# lamp_controller.net
KiCad netlist of a schematic drawn in Altium Designer
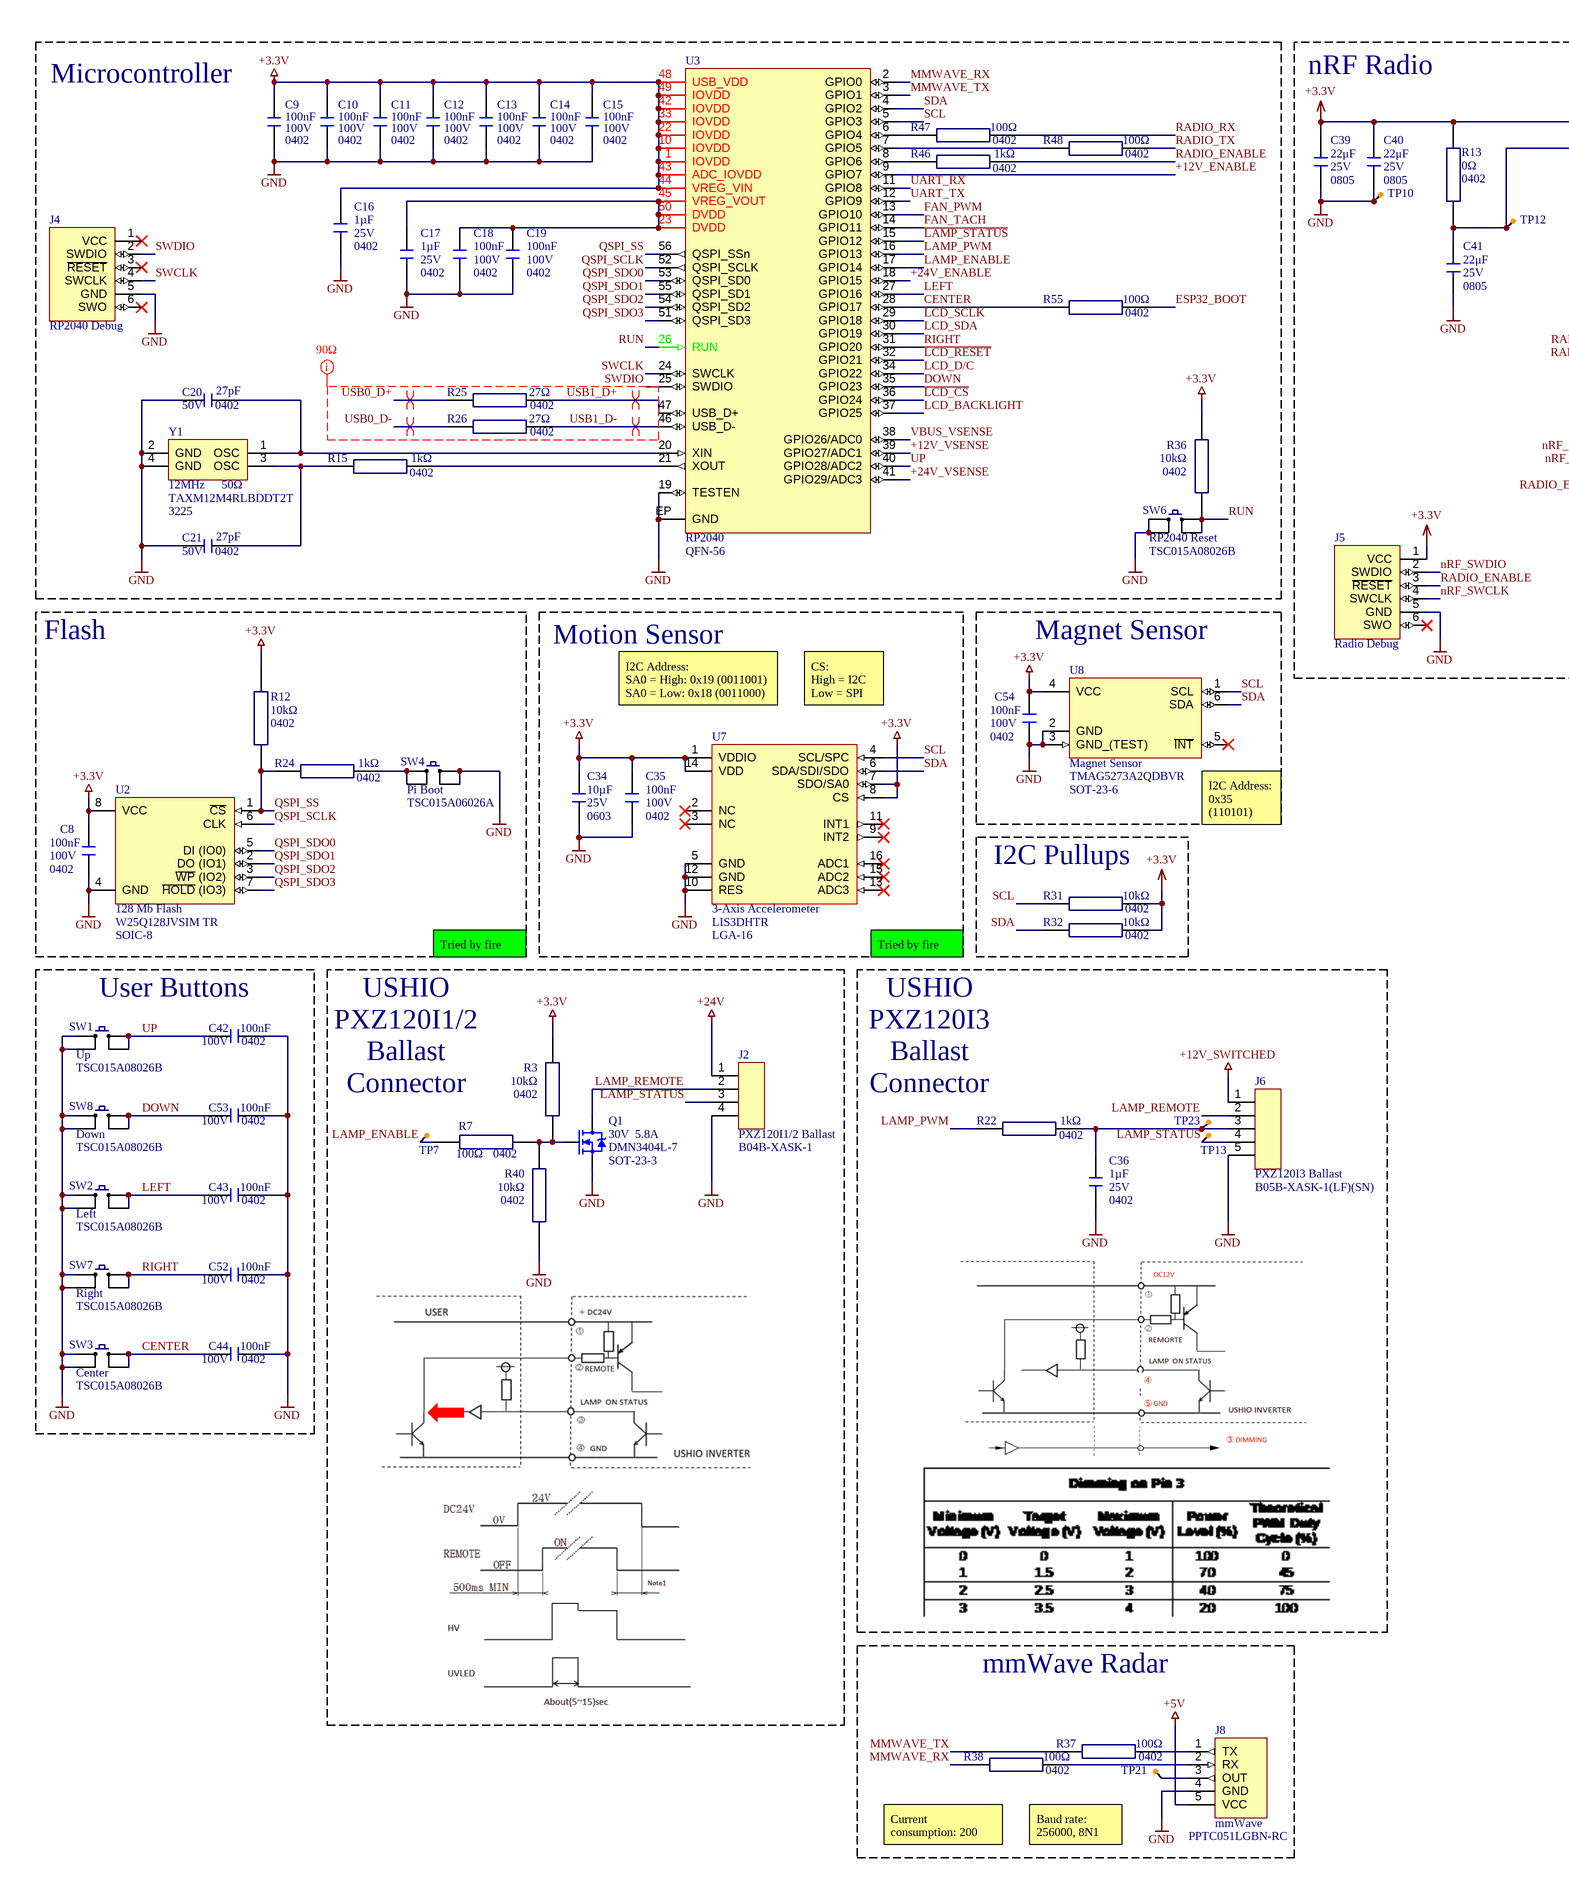
[diagram p0: lamp_controller.SchDoc, left]
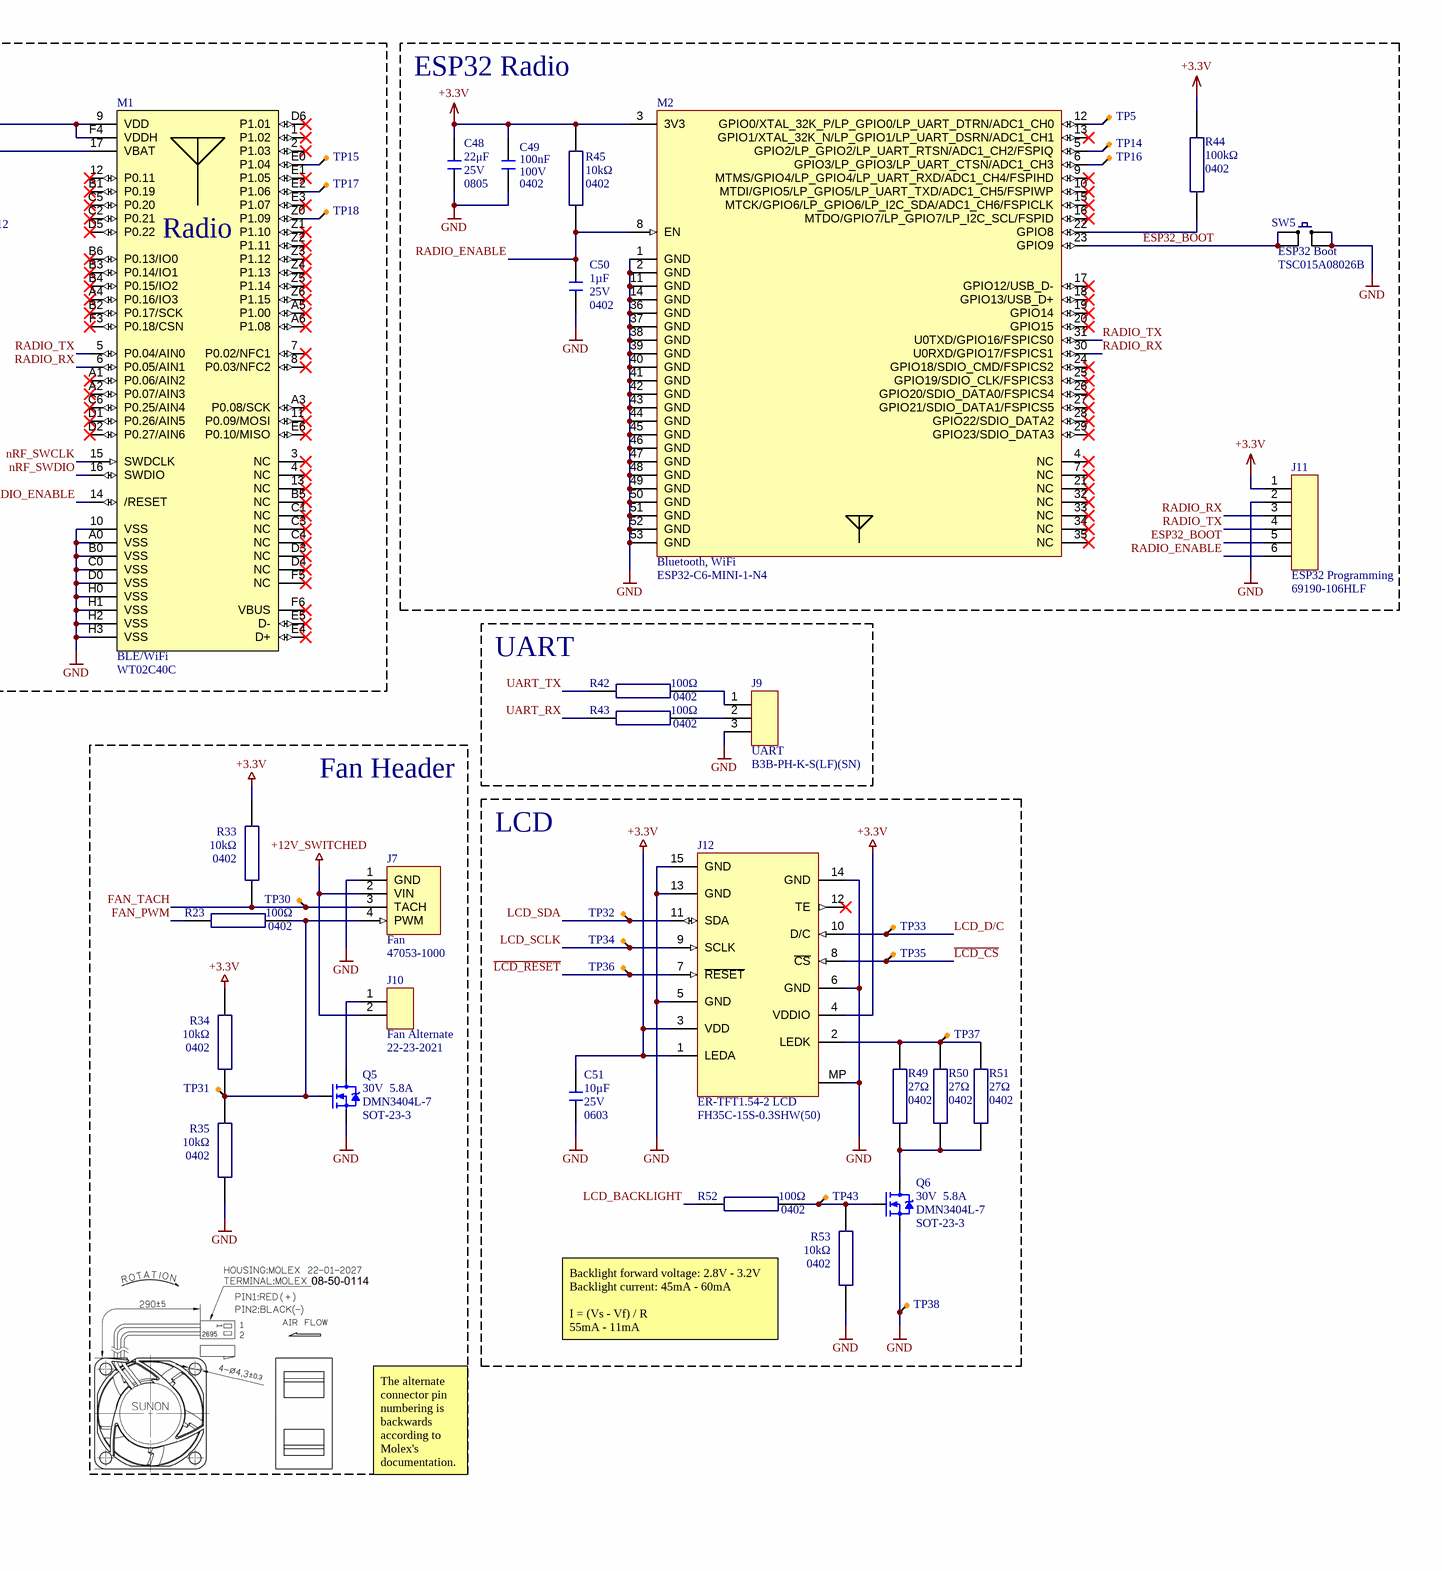
[diagram p1: lamp_controller.SchDoc, right]

(export (version "E")
  (design (tool "Eeschema 10.0.6"))
  (components
    (comp (ref "C8")
      (value "100nF")
      (footprint "0402_capacitor")
      (description "100 nF, 100 V, X7R, 0402 Chip capacitor")
      (fields
        (field (name "MANUFACTURER") "Murata")
        (field (name "CASE/PACKAGE") "0402")
        (field (name "MANUFACTURER PART NUMBER") "GRM155R62A104KE14D")
        (field (name "RATED DC VOLTAGE (URDC)") "100V")
      )
      (libsource (lib "lamp_controller") (part "GRM155R62A104KE14D"))
    )
    (comp (ref "C9")
      (value "100nF")
      (footprint "0402_capacitor")
      (description "100 nF, 100 V, X7R, 0402 Chip capacitor")
      (fields
        (field (name "MANUFACTURER") "Murata")
        (field (name "CASE/PACKAGE") "0402")
        (field (name "MANUFACTURER PART NUMBER") "GRM155R62A104KE14D")
        (field (name "RATED DC VOLTAGE (URDC)") "100V")
      )
      (libsource (lib "lamp_controller") (part "GRM155R62A104KE14D"))
    )
    (comp (ref "C10")
      (value "100nF")
      (footprint "0402_capacitor")
      (description "100 nF, 100 V, X7R, 0402 Chip capacitor")
      (fields
        (field (name "MANUFACTURER") "Murata")
        (field (name "CASE/PACKAGE") "0402")
        (field (name "MANUFACTURER PART NUMBER") "GRM155R62A104KE14D")
        (field (name "RATED DC VOLTAGE (URDC)") "100V")
      )
      (libsource (lib "lamp_controller") (part "GRM155R62A104KE14D"))
    )
    (comp (ref "C11")
      (value "100nF")
      (footprint "0402_capacitor")
      (description "100 nF, 100 V, X7R, 0402 Chip capacitor")
      (fields
        (field (name "MANUFACTURER") "Murata")
        (field (name "CASE/PACKAGE") "0402")
        (field (name "MANUFACTURER PART NUMBER") "GRM155R62A104KE14D")
        (field (name "RATED DC VOLTAGE (URDC)") "100V")
      )
      (libsource (lib "lamp_controller") (part "GRM155R62A104KE14D"))
    )
    (comp (ref "C12")
      (value "100nF")
      (footprint "0402_capacitor")
      (description "100 nF, 100 V, X7R, 0402 Chip capacitor")
      (fields
        (field (name "MANUFACTURER") "Murata")
        (field (name "CASE/PACKAGE") "0402")
        (field (name "MANUFACTURER PART NUMBER") "GRM155R62A104KE14D")
        (field (name "RATED DC VOLTAGE (URDC)") "100V")
      )
      (libsource (lib "lamp_controller") (part "GRM155R62A104KE14D"))
    )
    (comp (ref "C13")
      (value "100nF")
      (footprint "0402_capacitor")
      (description "100 nF, 100 V, X7R, 0402 Chip capacitor")
      (fields
        (field (name "MANUFACTURER") "Murata")
        (field (name "CASE/PACKAGE") "0402")
        (field (name "MANUFACTURER PART NUMBER") "GRM155R62A104KE14D")
        (field (name "RATED DC VOLTAGE (URDC)") "100V")
      )
      (libsource (lib "lamp_controller") (part "GRM155R62A104KE14D"))
    )
    (comp (ref "C14")
      (value "100nF")
      (footprint "0402_capacitor")
      (description "100 nF, 100 V, X7R, 0402 Chip capacitor")
      (fields
        (field (name "MANUFACTURER") "Murata")
        (field (name "CASE/PACKAGE") "0402")
        (field (name "MANUFACTURER PART NUMBER") "GRM155R62A104KE14D")
        (field (name "RATED DC VOLTAGE (URDC)") "100V")
      )
      (libsource (lib "lamp_controller") (part "GRM155R62A104KE14D"))
    )
    (comp (ref "C15")
      (value "100nF")
      (footprint "0402_capacitor")
      (description "100 nF, 100 V, X7R, 0402 Chip capacitor")
      (fields
        (field (name "MANUFACTURER") "Murata")
        (field (name "CASE/PACKAGE") "0402")
        (field (name "MANUFACTURER PART NUMBER") "GRM155R62A104KE14D")
        (field (name "RATED DC VOLTAGE (URDC)") "100V")
      )
      (libsource (lib "lamp_controller") (part "GRM155R62A104KE14D"))
    )
    (comp (ref "C16")
      (value "GRM155R61E105KA12D")
      (footprint "0402_capacitor")
      (description "1 µF, 25 V, X5R, 0402 Chip capacitor")
      (fields
        (field (name "MANUFACTURER") "Murata")
        (field (name "HOUSE_PART_NUMBER") "C-1uF-0402-002")
        (field (name "SIZE CODE") "0402")
        (field (name "CAPACITANCE") "1µF")
        (field (name "VOLTAGE") "25V")
      )
      (libsource (lib "lamp_controller") (part "GRM155R61E105KA12D"))
    )
    (comp (ref "C17")
      (value "GRM155R61E105KA12D")
      (footprint "0402_capacitor")
      (description "1 µF, 25 V, X5R, 0402 Chip capacitor")
      (fields
        (field (name "MANUFACTURER") "Murata")
        (field (name "HOUSE_PART_NUMBER") "C-1uF-0402-002")
        (field (name "SIZE CODE") "0402")
        (field (name "CAPACITANCE") "1µF")
        (field (name "VOLTAGE") "25V")
      )
      (libsource (lib "lamp_controller") (part "GRM155R61E105KA12D"))
    )
    (comp (ref "C18")
      (value "100nF")
      (footprint "0402_capacitor")
      (description "100 nF, 100 V, X7R, 0402 Chip capacitor")
      (fields
        (field (name "MANUFACTURER") "Murata")
        (field (name "CASE/PACKAGE") "0402")
        (field (name "MANUFACTURER PART NUMBER") "GRM155R62A104KE14D")
        (field (name "RATED DC VOLTAGE (URDC)") "100V")
      )
      (libsource (lib "lamp_controller") (part "GRM155R62A104KE14D"))
    )
    (comp (ref "C19")
      (value "100nF")
      (footprint "0402_capacitor")
      (description "100 nF, 100 V, X7R, 0402 Chip capacitor")
      (fields
        (field (name "MANUFACTURER") "Murata")
        (field (name "CASE/PACKAGE") "0402")
        (field (name "MANUFACTURER PART NUMBER") "GRM155R62A104KE14D")
        (field (name "RATED DC VOLTAGE (URDC)") "100V")
      )
      (libsource (lib "lamp_controller") (part "GRM155R62A104KE14D"))
    )
    (comp (ref "C20")
      (value "27pF")
      (footprint "0402_capacitor")
      (description "27 pF, 25 V, X7R, 0402 Chip capacitor")
      (fields
        (field (name "MANUFACTURER") "Yageo")
        (field (name "MANUFACTURER PART NUMBER") "CC0402JRNPO9BN270")
        (field (name "CASE/PACKAGE") "0402")
        (field (name "VOLTAGE RATING (DC)") "50V")
      )
      (libsource (lib "lamp_controller") (part "CC0402JRNPO9BN270"))
    )
    (comp (ref "C21")
      (value "27pF")
      (footprint "0402_capacitor")
      (description "27 pF, 25 V, X7R, 0402 Chip capacitor")
      (fields
        (field (name "MANUFACTURER") "Yageo")
        (field (name "MANUFACTURER PART NUMBER") "CC0402JRNPO9BN270")
        (field (name "CASE/PACKAGE") "0402")
        (field (name "VOLTAGE RATING (DC)") "50V")
      )
      (libsource (lib "lamp_controller") (part "CC0402JRNPO9BN270"))
    )
    (comp (ref "C34")
      (value "10µF")
      (footprint "0603_capacitor")
      (description "10 µF, 25 V, X5R, 0603 Chip capacitor")
      (fields
        (field (name "MANUFACTURER") "Samsung")
        (field (name "CASE/PACKAGE") "0603")
        (field (name "TOLERANCE") "20%")
        (field (name "VOLTAGE RATING") "25V")
      )
      (libsource (lib "lamp_controller") (part "CL10A106MA8NRNC"))
    )
    (comp (ref "C35")
      (value "100nF")
      (footprint "0402_capacitor")
      (description "100 nF, 100 V, X7R, 0402 Chip capacitor")
      (fields
        (field (name "MANUFACTURER") "Murata")
        (field (name "CASE/PACKAGE") "0402")
        (field (name "MANUFACTURER PART NUMBER") "GRM155R62A104KE14D")
        (field (name "RATED DC VOLTAGE (URDC)") "100V")
      )
      (libsource (lib "lamp_controller") (part "GRM155R62A104KE14D"))
    )
    (comp (ref "C36")
      (value "GRM155R61E105KA12D")
      (footprint "0402_capacitor")
      (description "1 µF, 25 V, X5R, 0402 Chip capacitor")
      (fields
        (field (name "MANUFACTURER") "Murata")
        (field (name "HOUSE_PART_NUMBER") "C-1uF-0402-002")
        (field (name "SIZE CODE") "0402")
        (field (name "CAPACITANCE") "1µF")
        (field (name "VOLTAGE") "25V")
      )
      (libsource (lib "lamp_controller") (part "GRM155R61E105KA12D"))
    )
    (comp (ref "C39")
      (value "22μF")
      (footprint "0805_capacitor")
      (description "22 μF, 25 V, X5R, 0805 Chip capacitor")
      (fields
        (field (name "MANUFACTURER") "Murata")
        (field (name "MANUFACTURER PART NUMBER") "GRT21BR61E226ME13L")
        (field (name "RATED DC VOLTAGE (URDC)") "25V")
        (field (name "CASE/PACKAGE") "0805")
      )
      (libsource (lib "lamp_controller") (part "GRT21BR61E226ME13L"))
    )
    (comp (ref "C40")
      (value "22μF")
      (footprint "0805_capacitor")
      (description "22 μF, 25 V, X5R, 0805 Chip capacitor")
      (fields
        (field (name "MANUFACTURER") "Murata")
        (field (name "MANUFACTURER PART NUMBER") "GRT21BR61E226ME13L")
        (field (name "RATED DC VOLTAGE (URDC)") "25V")
        (field (name "CASE/PACKAGE") "0805")
      )
      (libsource (lib "lamp_controller") (part "GRT21BR61E226ME13L"))
    )
    (comp (ref "C41")
      (value "22μF")
      (footprint "0805_capacitor")
      (description "22 μF, 25 V, X5R, 0805 Chip capacitor")
      (fields
        (field (name "MANUFACTURER") "Murata")
        (field (name "MANUFACTURER PART NUMBER") "GRT21BR61E226ME13L")
        (field (name "RATED DC VOLTAGE (URDC)") "25V")
        (field (name "CASE/PACKAGE") "0805")
      )
      (libsource (lib "lamp_controller") (part "GRT21BR61E226ME13L"))
    )
    (comp (ref "C42")
      (value "100nF")
      (footprint "0402_capacitor")
      (description "100 nF, 100 V, X7R, 0402 Chip capacitor")
      (fields
        (field (name "MANUFACTURER") "Murata")
        (field (name "CASE/PACKAGE") "0402")
        (field (name "MANUFACTURER PART NUMBER") "GRM155R62A104KE14D")
        (field (name "RATED DC VOLTAGE (URDC)") "100V")
      )
      (libsource (lib "lamp_controller") (part "GRM155R62A104KE14D"))
    )
    (comp (ref "C43")
      (value "100nF")
      (footprint "0402_capacitor")
      (description "100 nF, 100 V, X7R, 0402 Chip capacitor")
      (fields
        (field (name "MANUFACTURER") "Murata")
        (field (name "CASE/PACKAGE") "0402")
        (field (name "MANUFACTURER PART NUMBER") "GRM155R62A104KE14D")
        (field (name "RATED DC VOLTAGE (URDC)") "100V")
      )
      (libsource (lib "lamp_controller") (part "GRM155R62A104KE14D"))
    )
    (comp (ref "C44")
      (value "100nF")
      (footprint "0402_capacitor")
      (description "100 nF, 100 V, X7R, 0402 Chip capacitor")
      (fields
        (field (name "MANUFACTURER") "Murata")
        (field (name "CASE/PACKAGE") "0402")
        (field (name "MANUFACTURER PART NUMBER") "GRM155R62A104KE14D")
        (field (name "RATED DC VOLTAGE (URDC)") "100V")
      )
      (libsource (lib "lamp_controller") (part "GRM155R62A104KE14D"))
    )
    (comp (ref "C48")
      (value "22μF")
      (footprint "0805_capacitor")
      (description "22 μF, 25 V, X5R, 0805 Chip capacitor")
      (fields
        (field (name "MANUFACTURER") "Murata")
        (field (name "MANUFACTURER PART NUMBER") "GRT21BR61E226ME13L")
        (field (name "RATED DC VOLTAGE (URDC)") "25V")
        (field (name "CASE/PACKAGE") "0805")
      )
      (libsource (lib "lamp_controller") (part "GRT21BR61E226ME13L"))
    )
    (comp (ref "C49")
      (value "100nF")
      (footprint "0402_capacitor")
      (description "100 nF, 100 V, X7R, 0402 Chip capacitor")
      (fields
        (field (name "MANUFACTURER") "Murata")
        (field (name "CASE/PACKAGE") "0402")
        (field (name "MANUFACTURER PART NUMBER") "GRM155R62A104KE14D")
        (field (name "RATED DC VOLTAGE (URDC)") "100V")
      )
      (libsource (lib "lamp_controller") (part "GRM155R62A104KE14D"))
    )
    (comp (ref "C50")
      (value "GRM155R61E105KA12D")
      (footprint "0402_capacitor")
      (description "1 µF, 25 V, X5R, 0402 Chip capacitor")
      (fields
        (field (name "MANUFACTURER") "Murata")
        (field (name "HOUSE_PART_NUMBER") "C-1uF-0402-002")
        (field (name "SIZE CODE") "0402")
        (field (name "CAPACITANCE") "1µF")
        (field (name "VOLTAGE") "25V")
      )
      (libsource (lib "lamp_controller") (part "GRM155R61E105KA12D"))
    )
    (comp (ref "C51")
      (value "10µF")
      (footprint "0603_capacitor")
      (description "10 µF, 25 V, X5R, 0603 Chip capacitor")
      (fields
        (field (name "MANUFACTURER") "Samsung")
        (field (name "CASE/PACKAGE") "0603")
        (field (name "TOLERANCE") "20%")
        (field (name "VOLTAGE RATING") "25V")
      )
      (libsource (lib "lamp_controller") (part "CL10A106MA8NRNC"))
    )
    (comp (ref "C52")
      (value "100nF")
      (footprint "0402_capacitor")
      (description "100 nF, 100 V, X7R, 0402 Chip capacitor")
      (fields
        (field (name "MANUFACTURER") "Murata")
        (field (name "CASE/PACKAGE") "0402")
        (field (name "MANUFACTURER PART NUMBER") "GRM155R62A104KE14D")
        (field (name "RATED DC VOLTAGE (URDC)") "100V")
      )
      (libsource (lib "lamp_controller") (part "GRM155R62A104KE14D"))
    )
    (comp (ref "C53")
      (value "100nF")
      (footprint "0402_capacitor")
      (description "100 nF, 100 V, X7R, 0402 Chip capacitor")
      (fields
        (field (name "MANUFACTURER") "Murata")
        (field (name "CASE/PACKAGE") "0402")
        (field (name "MANUFACTURER PART NUMBER") "GRM155R62A104KE14D")
        (field (name "RATED DC VOLTAGE (URDC)") "100V")
      )
      (libsource (lib "lamp_controller") (part "GRM155R62A104KE14D"))
    )
    (comp (ref "C54")
      (value "100nF")
      (footprint "0402_capacitor")
      (description "100 nF, 100 V, X7R, 0402 Chip capacitor")
      (fields
        (field (name "MANUFACTURER") "Murata")
        (field (name "CASE/PACKAGE") "0402")
        (field (name "MANUFACTURER PART NUMBER") "GRM155R62A104KE14D")
        (field (name "RATED DC VOLTAGE (URDC)") "100V")
      )
      (libsource (lib "lamp_controller") (part "GRM155R62A104KE14D"))
    )
    (comp (ref "J2")
      (value "PXZ120I1/2 Ballast")
      (footprint "B04B-XASK-1")
      (description "4-pin JST XA header, 2.5mm pitch, through-hole")
      (fields (field (name "MANUFACTURER") "JST") (field (name "MANUFACTURER PART NUMBER") "B04B-XASK-1"))
      (libsource (lib "lamp_controller") (part "B04B-XASK-1"))
    )
    (comp (ref "J4")
      (value "RP2040 Debug")
      (footprint "debug_header_dual")
      (description "Tag-connect 6-pin pogo header")
      (libsource (lib "lamp_controller") (part "debug_header"))
    )
    (comp (ref "J5")
      (value "Radio Debug")
      (footprint "debug_header_dual")
      (description "Tag-connect 6-pin pogo header")
      (libsource (lib "lamp_controller") (part "debug_header"))
    )
    (comp (ref "J6")
      (value "PXZ120I3 Ballast")
      (footprint "B05B-XASK-1")
      (description "5-Pin JST XA header, 2.5mm pitch, through-hole")
      (fields
        (field (name "MANUFACTURER") "JST")
        (field (name "MANUFACTURER PART NUMBER") "B05B-XASK-1(LF)(SN)")
      )
      (libsource (lib "lamp_controller") (part "B05B-XASK-1(LF)(SN)"))
    )
    (comp (ref "J7")
      (value "Fan")
      (footprint "470531000")
      (description "4-pin PC Fan connector")
      (fields (field (name "MANUFACTURER") "Molex") (field (name "MANUFACTURER PART NUMBER") "47053-1000"))
      (libsource (lib "lamp_controller") (part "470531000"))
    )
    (comp (ref "J8")
      (value "mmWave")
      (footprint "radar_angled_1")
      (description "5-Pin angled female header with mmWave radar board.")
      (fields
        (field (name "MANUFACTURER") "Sullins")
        (field (name "MANUFACTURER PART NUMBER") "PPTC051LGBN-RC")
      )
      (libsource (lib "lamp_controller") (part "PPTC051LGBN-RC"))
    )
    (comp (ref "J9")
      (value "UART")
      (footprint "B3B-PH-K-S(LF)(SN)")
      (description "3-Pin JST PH header, 2mm pitch, Through Hole")
      (fields
        (field (name "MANUFACTURER") "JST")
        (field (name "MANUFACTURER PART NUMBER") "B3B-PH-K-S(LF)(SN)")
      )
      (libsource (lib "lamp_controller") (part "B3B-PH-K-S(LF)(SN)"))
    )
    (comp (ref "J10")
      (value "Fan Alternate")
      (footprint "22012027")
      (description "2-Pin 0.1\" header, through-hole")
      (fields (field (name "MANUFACTURER") "Molex") (field (name "MANUFACTURER PART NUMBER") "22-23-2021"))
      (libsource (lib "lamp_controller") (part "22-23-2021"))
    )
    (comp (ref "J11")
      (value "ESP32 Programming")
      (footprint "69190-106HLF")
      (description "6-Pin 0.1\" unshrouded header pins")
      (fields
        (field (name "MANUFACTURER") "Amphenol ICC / FCI")
        (field (name "MANUFACTURER PART NUMBER") "69190-106HLF")
      )
      (libsource (lib "lamp_controller") (part "69190-106HLF"))
    )
    (comp (ref "J12")
      (value "ER-TFT1.54-2 LCD")
      (footprint "FH35C-15S-0.3SHW(50)")
      (description "ER-TFT1.54-2 1.54\" IPS LCD, 240x240, ST7789 controller, FH35C-15S-0.3SHW(50) connector")
      (fields
        (field (name "MANUFACTURER") "HRS")
        (field (name "MANUFACTURER PART NUMBER") "FH35C-15S-0.3SHW(50)")
      )
      (libsource (lib "lamp_controller") (part "LCD Connector"))
    )
    (comp (ref "M1")
      (value "BLE/WiFi")
      (footprint "WT02C40C")
      (description "nRF5340 BLE/WIFI module")
      (fields (field (name "MANUFACTURER PART NUMBER") "WT02C40C"))
      (libsource (lib "lamp_controller") (part "WT02C40C"))
    )
    (comp (ref "M2")
      (value "Bluetooth, WiFi")
      (footprint "ESP32-C6-MINI-1")
      (description "ESP32-C6 chipset, PCB antenna, SMD-53")
      (fields
        (field (name "MANUFACTURER") "Espressif Systems")
        (field (name "MANUFACTURER PART NUMBER") "ESP32-C6-MINI-1-N4")
      )
      (libsource (lib "lamp_controller") (part "ESP32-C6-MINI-1-N4"))
    )
    (comp (ref "Q1")
      (value "DMN3404L-7")
      (footprint "SOT-23-3")
      (description "N-FET, 30 V, 5.8 A, SOT-23-3")
      (fields
        (field (name "MANUFACTURER") "Diodes")
        (field (name "PACKAGE") "SOT-23-3")
        (field (name "DS BREAKDOWN VOLTAGE-MIN") "30V")
        (field (name "DRAIN CURRENT-MAX (ID)") "5.8A")
        (field (name "MANUFACTURER PART NUMBER") "DMN3404L-7")
      )
      (libsource (lib "lamp_controller") (part "DMN3404L-7"))
    )
    (comp (ref "Q5")
      (value "DMN3404L-7")
      (footprint "SOT-23-3")
      (description "N-FET, 30 V, 5.8 A, SOT-23-3")
      (fields
        (field (name "MANUFACTURER") "Diodes")
        (field (name "PACKAGE") "SOT-23-3")
        (field (name "DS BREAKDOWN VOLTAGE-MIN") "30V")
        (field (name "DRAIN CURRENT-MAX (ID)") "5.8A")
        (field (name "MANUFACTURER PART NUMBER") "DMN3404L-7")
      )
      (libsource (lib "lamp_controller") (part "DMN3404L-7"))
    )
    (comp (ref "Q6")
      (value "DMN3404L-7")
      (footprint "SOT-23-3")
      (description "N-FET, 30 V, 5.8 A, SOT-23-3")
      (fields
        (field (name "MANUFACTURER") "Diodes")
        (field (name "PACKAGE") "SOT-23-3")
        (field (name "DS BREAKDOWN VOLTAGE-MIN") "30V")
        (field (name "DRAIN CURRENT-MAX (ID)") "5.8A")
        (field (name "MANUFACTURER PART NUMBER") "DMN3404L-7")
      )
      (libsource (lib "lamp_controller") (part "DMN3404L-7"))
    )
    (comp (ref "R3")
      (value "RMCF0402FT10K0")
      (footprint "0402_resistor")
      (description "10 kΩ, 0402 Chip resistor")
      (fields
        (field (name "MANUFACTURER") "Stackpole Electronics")
        (field (name "TOLERANCE") "1%")
        (field (name "CASE CODE (IMPERIAL)") "0402")
        (field (name "RESISTANCE") "10kΩ")
      )
      (libsource (lib "lamp_controller") (part "RMCF0402FT10K0"))
    )
    (comp (ref "R7")
      (value "RMCF0402FT100R")
      (footprint "0402_resistor")
      (description "100 Ω, 0402 Chip resistor")
      (fields
        (field (name "MANUFACTURER") "Stackpole Electronics")
        (field (name "TOLERANCE") "1%")
        (field (name "CASE CODE (IMPERIAL)") "0402")
        (field (name "RESISTANCE") "100Ω")
      )
      (libsource (lib "lamp_controller") (part "RMCF0402FT100R"))
    )
    (comp (ref "R12")
      (value "RMCF0402FT10K0")
      (footprint "0402_resistor")
      (description "10 kΩ, 0402 Chip resistor")
      (fields
        (field (name "MANUFACTURER") "Stackpole Electronics")
        (field (name "TOLERANCE") "1%")
        (field (name "CASE CODE (IMPERIAL)") "0402")
        (field (name "RESISTANCE") "10kΩ")
      )
      (libsource (lib "lamp_controller") (part "RMCF0402FT10K0"))
    )
    (comp (ref "R13")
      (value "RMCF0402ZT0R00")
      (footprint "0402_resistor")
      (description "0 Ω, 0402 Jumper")
      (fields
        (field (name "MANUFACTURER") "Stackpole Electronics")
        (field (name "HOUSE_PART_NUMBER") "JP-0402-001")
        (field (name "RESISTANCE") "0Ω")
        (field (name "CASE/PACKAGE") "0402")
      )
      (libsource (lib "lamp_controller") (part "RMCF0402ZT0R00"))
    )
    (comp (ref "R15")
      (value "CR0402-FX-1001GLF")
      (footprint "0402_resistor")
      (description "1 kΩ, 0402 Chip resistor")
      (fields
        (field (name "MANUFACTURER") "Bourns")
        (field (name "TOLERANCE") "1%")
        (field (name "SIZE CODE") "0402")
        (field (name "RESISTANCE") "1kΩ")
      )
      (libsource (lib "lamp_controller") (part "CR0402-FX-1001GLF"))
    )
    (comp (ref "R22")
      (value "CR0402-FX-1001GLF")
      (footprint "0402_resistor")
      (description "1 kΩ, 0402 Chip resistor")
      (fields
        (field (name "MANUFACTURER") "Bourns")
        (field (name "TOLERANCE") "1%")
        (field (name "SIZE CODE") "0402")
        (field (name "RESISTANCE") "1kΩ")
      )
      (libsource (lib "lamp_controller") (part "CR0402-FX-1001GLF"))
    )
    (comp (ref "R23")
      (value "RMCF0402FT100R")
      (footprint "0402_resistor")
      (description "100 Ω, 0402 Chip resistor")
      (fields
        (field (name "MANUFACTURER") "Stackpole Electronics")
        (field (name "TOLERANCE") "1%")
        (field (name "CASE CODE (IMPERIAL)") "0402")
        (field (name "RESISTANCE") "100Ω")
      )
      (libsource (lib "lamp_controller") (part "RMCF0402FT100R"))
    )
    (comp (ref "R24")
      (value "CR0402-FX-1001GLF")
      (footprint "0402_resistor")
      (description "1 kΩ, 0402 Chip resistor")
      (fields
        (field (name "MANUFACTURER") "Bourns")
        (field (name "TOLERANCE") "1%")
        (field (name "SIZE CODE") "0402")
        (field (name "RESISTANCE") "1kΩ")
      )
      (libsource (lib "lamp_controller") (part "CR0402-FX-1001GLF"))
    )
    (comp (ref "R25")
      (value "RMCF0402FT27R0")
      (footprint "0402_resistor")
      (description "27 Ω, 0402 Chip resistor")
      (fields
        (field (name "MANUFACTURER") "Stackpole Electronics")
        (field (name "TOLERANCE") "1%")
        (field (name "RESISTANCE") "27Ω")
        (field (name "SIZE CODE") "0402")
      )
      (libsource (lib "lamp_controller") (part "RMCF0402FT27R0"))
    )
    (comp (ref "R26")
      (value "RMCF0402FT27R0")
      (footprint "0402_resistor")
      (description "27 Ω, 0402 Chip resistor")
      (fields
        (field (name "MANUFACTURER") "Stackpole Electronics")
        (field (name "TOLERANCE") "1%")
        (field (name "RESISTANCE") "27Ω")
        (field (name "SIZE CODE") "0402")
      )
      (libsource (lib "lamp_controller") (part "RMCF0402FT27R0"))
    )
    (comp (ref "R31")
      (value "RMCF0402FT10K0")
      (footprint "0402_resistor")
      (description "10 kΩ, 0402 Chip resistor")
      (fields
        (field (name "MANUFACTURER") "Stackpole Electronics")
        (field (name "TOLERANCE") "1%")
        (field (name "CASE CODE (IMPERIAL)") "0402")
        (field (name "RESISTANCE") "10kΩ")
      )
      (libsource (lib "lamp_controller") (part "RMCF0402FT10K0"))
    )
    (comp (ref "R32")
      (value "RMCF0402FT10K0")
      (footprint "0402_resistor")
      (description "10 kΩ, 0402 Chip resistor")
      (fields
        (field (name "MANUFACTURER") "Stackpole Electronics")
        (field (name "TOLERANCE") "1%")
        (field (name "CASE CODE (IMPERIAL)") "0402")
        (field (name "RESISTANCE") "10kΩ")
      )
      (libsource (lib "lamp_controller") (part "RMCF0402FT10K0"))
    )
    (comp (ref "R33")
      (value "RMCF0402FT10K0")
      (footprint "0402_resistor")
      (description "10 kΩ, 0402 Chip resistor")
      (fields
        (field (name "MANUFACTURER") "Stackpole Electronics")
        (field (name "TOLERANCE") "1%")
        (field (name "CASE CODE (IMPERIAL)") "0402")
        (field (name "RESISTANCE") "10kΩ")
      )
      (libsource (lib "lamp_controller") (part "RMCF0402FT10K0"))
    )
    (comp (ref "R34")
      (value "RMCF0402FT10K0")
      (footprint "0402_resistor")
      (description "10 kΩ, 0402 Chip resistor")
      (fields
        (field (name "MANUFACTURER") "Stackpole Electronics")
        (field (name "TOLERANCE") "1%")
        (field (name "CASE CODE (IMPERIAL)") "0402")
        (field (name "RESISTANCE") "10kΩ")
      )
      (libsource (lib "lamp_controller") (part "RMCF0402FT10K0"))
    )
    (comp (ref "R35")
      (value "RMCF0402FT10K0")
      (footprint "0402_resistor")
      (description "10 kΩ, 0402 Chip resistor")
      (fields
        (field (name "MANUFACTURER") "Stackpole Electronics")
        (field (name "TOLERANCE") "1%")
        (field (name "CASE CODE (IMPERIAL)") "0402")
        (field (name "RESISTANCE") "10kΩ")
      )
      (libsource (lib "lamp_controller") (part "RMCF0402FT10K0"))
    )
    (comp (ref "R36")
      (value "RMCF0402FT10K0")
      (footprint "0402_resistor")
      (description "10 kΩ, 0402 Chip resistor")
      (fields
        (field (name "MANUFACTURER") "Stackpole Electronics")
        (field (name "TOLERANCE") "1%")
        (field (name "CASE CODE (IMPERIAL)") "0402")
        (field (name "RESISTANCE") "10kΩ")
      )
      (libsource (lib "lamp_controller") (part "RMCF0402FT10K0"))
    )
    (comp (ref "R37")
      (value "RMCF0402FT100R")
      (footprint "0402_resistor")
      (description "100 Ω, 0402 Chip resistor")
      (fields
        (field (name "MANUFACTURER") "Stackpole Electronics")
        (field (name "TOLERANCE") "1%")
        (field (name "CASE CODE (IMPERIAL)") "0402")
        (field (name "RESISTANCE") "100Ω")
      )
      (libsource (lib "lamp_controller") (part "RMCF0402FT100R"))
    )
    (comp (ref "R38")
      (value "RMCF0402FT100R")
      (footprint "0402_resistor")
      (description "100 Ω, 0402 Chip resistor")
      (fields
        (field (name "MANUFACTURER") "Stackpole Electronics")
        (field (name "TOLERANCE") "1%")
        (field (name "CASE CODE (IMPERIAL)") "0402")
        (field (name "RESISTANCE") "100Ω")
      )
      (libsource (lib "lamp_controller") (part "RMCF0402FT100R"))
    )
    (comp (ref "R40")
      (value "RMCF0402FT10K0")
      (footprint "0402_resistor")
      (description "10 kΩ, 0402 Chip resistor")
      (fields
        (field (name "MANUFACTURER") "Stackpole Electronics")
        (field (name "TOLERANCE") "1%")
        (field (name "CASE CODE (IMPERIAL)") "0402")
        (field (name "RESISTANCE") "10kΩ")
      )
      (libsource (lib "lamp_controller") (part "RMCF0402FT10K0"))
    )
    (comp (ref "R42")
      (value "RMCF0402FT100R")
      (footprint "0402_resistor")
      (description "100 Ω, 0402 Chip resistor")
      (fields
        (field (name "MANUFACTURER") "Stackpole Electronics")
        (field (name "TOLERANCE") "1%")
        (field (name "CASE CODE (IMPERIAL)") "0402")
        (field (name "RESISTANCE") "100Ω")
      )
      (libsource (lib "lamp_controller") (part "RMCF0402FT100R"))
    )
    (comp (ref "R43")
      (value "RMCF0402FT100R")
      (footprint "0402_resistor")
      (description "100 Ω, 0402 Chip resistor")
      (fields
        (field (name "MANUFACTURER") "Stackpole Electronics")
        (field (name "TOLERANCE") "1%")
        (field (name "CASE CODE (IMPERIAL)") "0402")
        (field (name "RESISTANCE") "100Ω")
      )
      (libsource (lib "lamp_controller") (part "RMCF0402FT100R"))
    )
    (comp (ref "R44")
      (value "100kΩ")
      (footprint "0402_resistor")
      (description "100 kΩ, 0402 Chip resistor")
      (fields
        (field (name "MANUFACTURER") "Stackpole Electronics")
        (field (name "MANUFACTURER PART NUMBER") "RMCF0402FT100K")
        (field (name "CASE/PACKAGE") "0402")
      )
      (libsource (lib "lamp_controller") (part "RMCF0402FT100K"))
    )
    (comp (ref "R45")
      (value "RMCF0402FT10K0")
      (footprint "0402_resistor")
      (description "10 kΩ, 0402 Chip resistor")
      (fields
        (field (name "MANUFACTURER") "Stackpole Electronics")
        (field (name "TOLERANCE") "1%")
        (field (name "CASE CODE (IMPERIAL)") "0402")
        (field (name "RESISTANCE") "10kΩ")
      )
      (libsource (lib "lamp_controller") (part "RMCF0402FT10K0"))
    )
    (comp (ref "R46")
      (value "CR0402-FX-1001GLF")
      (footprint "0402_resistor")
      (description "1 kΩ, 0402 Chip resistor")
      (fields
        (field (name "MANUFACTURER") "Bourns")
        (field (name "TOLERANCE") "1%")
        (field (name "SIZE CODE") "0402")
        (field (name "RESISTANCE") "1kΩ")
      )
      (libsource (lib "lamp_controller") (part "CR0402-FX-1001GLF"))
    )
    (comp (ref "R47")
      (value "RMCF0402FT100R")
      (footprint "0402_resistor")
      (description "100 Ω, 0402 Chip resistor")
      (fields
        (field (name "MANUFACTURER") "Stackpole Electronics")
        (field (name "TOLERANCE") "1%")
        (field (name "CASE CODE (IMPERIAL)") "0402")
        (field (name "RESISTANCE") "100Ω")
      )
      (libsource (lib "lamp_controller") (part "RMCF0402FT100R"))
    )
    (comp (ref "R48")
      (value "RMCF0402FT100R")
      (footprint "0402_resistor")
      (description "100 Ω, 0402 Chip resistor")
      (fields
        (field (name "MANUFACTURER") "Stackpole Electronics")
        (field (name "TOLERANCE") "1%")
        (field (name "CASE CODE (IMPERIAL)") "0402")
        (field (name "RESISTANCE") "100Ω")
      )
      (libsource (lib "lamp_controller") (part "RMCF0402FT100R"))
    )
    (comp (ref "R49")
      (value "RMCF0402FT27R0")
      (footprint "0402_resistor")
      (description "27 Ω, 0402 Chip resistor")
      (fields
        (field (name "MANUFACTURER") "Stackpole Electronics")
        (field (name "TOLERANCE") "1%")
        (field (name "RESISTANCE") "27Ω")
        (field (name "SIZE CODE") "0402")
      )
      (libsource (lib "lamp_controller") (part "RMCF0402FT27R0"))
    )
    (comp (ref "R50")
      (value "RMCF0402FT27R0")
      (footprint "0402_resistor")
      (description "27 Ω, 0402 Chip resistor")
      (fields
        (field (name "MANUFACTURER") "Stackpole Electronics")
        (field (name "TOLERANCE") "1%")
        (field (name "RESISTANCE") "27Ω")
        (field (name "SIZE CODE") "0402")
      )
      (libsource (lib "lamp_controller") (part "RMCF0402FT27R0"))
    )
    (comp (ref "R51")
      (value "RMCF0402FT27R0")
      (footprint "0402_resistor")
      (description "27 Ω, 0402 Chip resistor")
      (fields
        (field (name "MANUFACTURER") "Stackpole Electronics")
        (field (name "TOLERANCE") "1%")
        (field (name "RESISTANCE") "27Ω")
        (field (name "SIZE CODE") "0402")
      )
      (libsource (lib "lamp_controller") (part "RMCF0402FT27R0"))
    )
    (comp (ref "R52")
      (value "RMCF0402FT100R")
      (footprint "0402_resistor")
      (description "100 Ω, 0402 Chip resistor")
      (fields
        (field (name "MANUFACTURER") "Stackpole Electronics")
        (field (name "TOLERANCE") "1%")
        (field (name "CASE CODE (IMPERIAL)") "0402")
        (field (name "RESISTANCE") "100Ω")
      )
      (libsource (lib "lamp_controller") (part "RMCF0402FT100R"))
    )
    (comp (ref "R53")
      (value "RMCF0402FT10K0")
      (footprint "0402_resistor")
      (description "10 kΩ, 0402 Chip resistor")
      (fields
        (field (name "MANUFACTURER") "Stackpole Electronics")
        (field (name "TOLERANCE") "1%")
        (field (name "CASE CODE (IMPERIAL)") "0402")
        (field (name "RESISTANCE") "10kΩ")
      )
      (libsource (lib "lamp_controller") (part "RMCF0402FT10K0"))
    )
    (comp (ref "R55")
      (value "RMCF0402FT100R")
      (footprint "0402_resistor")
      (description "100 Ω, 0402 Chip resistor")
      (fields
        (field (name "MANUFACTURER") "Stackpole Electronics")
        (field (name "TOLERANCE") "1%")
        (field (name "CASE CODE (IMPERIAL)") "0402")
        (field (name "RESISTANCE") "100Ω")
      )
      (libsource (lib "lamp_controller") (part "RMCF0402FT100R"))
    )
    (comp (ref "SW1")
      (value "Up")
      (footprint "TSC015A08026B")
      (description "Tactile switch, SPST")
      (fields
        (field (name "HOUSE_PART_NUMBER") "SW-TAC-4.5-8-260gf")
        (field (name "MANUFACTURER PART NUMBER") "TSC015A08026B")
      )
      (libsource (lib "lamp_controller") (part "TSC015A08026B"))
    )
    (comp (ref "SW2")
      (value "Left")
      (footprint "TSC015A08026B")
      (description "Tactile switch, SPST")
      (fields
        (field (name "HOUSE_PART_NUMBER") "SW-TAC-4.5-8-260gf")
        (field (name "MANUFACTURER PART NUMBER") "TSC015A08026B")
      )
      (libsource (lib "lamp_controller") (part "TSC015A08026B"))
    )
    (comp (ref "SW3")
      (value "Center")
      (footprint "TSC015A08026B")
      (description "Tactile switch, SPST")
      (fields
        (field (name "HOUSE_PART_NUMBER") "SW-TAC-4.5-8-260gf")
        (field (name "MANUFACTURER PART NUMBER") "TSC015A08026B")
      )
      (libsource (lib "lamp_controller") (part "TSC015A08026B"))
    )
    (comp (ref "SW4")
      (value "Pi Boot")
      (footprint "TSC015A06026A")
      (description "Tactile switch, SPST, 6mm tall")
      (fields (field (name "MANUFACTURER PART NUMBER") "TSC015A06026A"))
      (libsource (lib "lamp_controller") (part "TSC015A06026A"))
    )
    (comp (ref "SW5")
      (value "ESP32 Boot")
      (footprint "TSC015A08026B")
      (description "Tactile switch, SPST")
      (fields
        (field (name "HOUSE_PART_NUMBER") "SW-TAC-4.5-8-260gf")
        (field (name "MANUFACTURER PART NUMBER") "TSC015A08026B")
      )
      (libsource (lib "lamp_controller") (part "TSC015A08026B"))
    )
    (comp (ref "SW6")
      (value "RP2040 Reset")
      (footprint "TSC015A08026B")
      (description "Tactile switch, SPST")
      (fields
        (field (name "HOUSE_PART_NUMBER") "SW-TAC-4.5-8-260gf")
        (field (name "MANUFACTURER PART NUMBER") "TSC015A08026B")
      )
      (libsource (lib "lamp_controller") (part "TSC015A08026B"))
    )
    (comp (ref "SW7")
      (value "Right")
      (footprint "TSC015A08026B")
      (description "Tactile switch, SPST")
      (fields
        (field (name "HOUSE_PART_NUMBER") "SW-TAC-4.5-8-260gf")
        (field (name "MANUFACTURER PART NUMBER") "TSC015A08026B")
      )
      (libsource (lib "lamp_controller") (part "TSC015A08026B"))
    )
    (comp (ref "SW8")
      (value "Down")
      (footprint "TSC015A08026B")
      (description "Tactile switch, SPST")
      (fields
        (field (name "HOUSE_PART_NUMBER") "SW-TAC-4.5-8-260gf")
        (field (name "MANUFACTURER PART NUMBER") "TSC015A08026B")
      )
      (libsource (lib "lamp_controller") (part "TSC015A08026B"))
    )
    (comp (ref "TP5")
      (value "*")
      (footprint "test_point-1")
      (description "Test point")
      (libsource (lib "lamp_controller") (part "test_point-1"))
    )
    (comp (ref "TP7")
      (value "Lamp Enable")
      (footprint "test_point-1")
      (description "Test point")
      (libsource (lib "lamp_controller") (part "test_point-1"))
    )
    (comp (ref "TP10")
      (value "GND")
      (footprint "test_point-1")
      (description "Test point")
      (libsource (lib "lamp_controller") (part "test_point-1"))
    )
    (comp (ref "TP12")
      (value "nRF_VBAT")
      (footprint "test_point-1")
      (description "Test point")
      (libsource (lib "lamp_controller") (part "test_point-1"))
    )
    (comp (ref "TP13")
      (value "Lamp Status")
      (footprint "test_point-1")
      (description "Test point")
      (libsource (lib "lamp_controller") (part "test_point-1"))
    )
    (comp (ref "TP14")
      (value "*")
      (footprint "test_point-1")
      (description "Test point")
      (libsource (lib "lamp_controller") (part "test_point-1"))
    )
    (comp (ref "TP15")
      (value "*")
      (footprint "test_point-1")
      (description "Test point")
      (libsource (lib "lamp_controller") (part "test_point-1"))
    )
    (comp (ref "TP16")
      (value "*")
      (footprint "test_point-1")
      (description "Test point")
      (libsource (lib "lamp_controller") (part "test_point-1"))
    )
    (comp (ref "TP17")
      (value "*")
      (footprint "test_point-1")
      (description "Test point")
      (libsource (lib "lamp_controller") (part "test_point-1"))
    )
    (comp (ref "TP18")
      (value "*")
      (footprint "test_point-1")
      (description "Test point")
      (libsource (lib "lamp_controller") (part "test_point-1"))
    )
    (comp (ref "TP21")
      (value "RADAR Out")
      (footprint "test_point-1")
      (description "Test point")
      (libsource (lib "lamp_controller") (part "test_point-1"))
    )
    (comp (ref "TP23")
      (value "nRF_VBAT")
      (footprint "test_point-1")
      (description "Test point")
      (libsource (lib "lamp_controller") (part "test_point-1"))
    )
    (comp (ref "TP30")
      (value "Fan Tach")
      (footprint "test_point-1")
      (description "Test point")
      (libsource (lib "lamp_controller") (part "test_point-1"))
    )
    (comp (ref "TP31")
      (value "Fan PWM")
      (footprint "test_point-1")
      (description "Test point")
      (libsource (lib "lamp_controller") (part "test_point-1"))
    )
    (comp (ref "TP32")
      (value "LCD SDA")
      (footprint "test_point-1")
      (description "Test point")
      (libsource (lib "lamp_controller") (part "test_point-1"))
    )
    (comp (ref "TP33")
      (value "LCD D/C")
      (footprint "test_point-1")
      (description "Test point")
      (libsource (lib "lamp_controller") (part "test_point-1"))
    )
    (comp (ref "TP34")
      (value "LCD SCLK")
      (footprint "test_point-1")
      (description "Test point")
      (libsource (lib "lamp_controller") (part "test_point-1"))
    )
    (comp (ref "TP35")
      (value "LCD CS")
      (footprint "test_point-1")
      (description "Test point")
      (libsource (lib "lamp_controller") (part "test_point-1"))
    )
    (comp (ref "TP36")
      (value "LCD Reset")
      (footprint "test_point-1")
      (description "Test point")
      (libsource (lib "lamp_controller") (part "test_point-1"))
    )
    (comp (ref "TP37")
      (value "LED K")
      (footprint "test_point-1")
      (description "Test point")
      (libsource (lib "lamp_controller") (part "test_point-1"))
    )
    (comp (ref "TP38")
      (value "GND")
      (footprint "test_point-1")
      (description "Test point")
      (libsource (lib "lamp_controller") (part "test_point-1"))
    )
    (comp (ref "TP43")
      (value "LCB Backlight")
      (footprint "test_point-1")
      (description "Test point")
      (libsource (lib "lamp_controller") (part "test_point-1"))
    )
    (comp (ref "U2")
      (value "128 Mb Flash")
      (footprint "SOIC-8_wide")
      (description "128Mb SPI flash memory")
      (fields
        (field (name "MANUFACTURER") "Winbond")
        (field (name "HOUSE_PART_NUMBER") "W25Q128JVSIM")
        (field (name "MANUFACTURER PART NUMBER") "W25Q128JVSIM TR")
        (field (name "CASE/PACKAGE") "SOIC-8")
      )
      (libsource (lib "lamp_controller") (part "W25Q128JVSIM TR"))
    )
    (comp (ref "U3")
      (value "RP2040")
      (footprint "QFN-56")
      (description "Raspberry Pi microcontroller, QFN-56")
      (fields
        (field (name "MANUFACTURER") "Raspberry Pi")
        (field (name "MANUFACTURER PART NUMBER") "RP2040")
        (field (name "PACKAGE") "QFN-56")
      )
      (libsource (lib "lamp_controller") (part "RP2040"))
    )
    (comp (ref "U7")
      (value "3-Axis Accelerometer")
      (footprint "LGA50P300X300X100-16N")
      (description "3-Axis accelerometer, 16-bit, I2C/SPI, LGA-16")
      (fields
        (field (name "MANUFACTURER") "STMicroelectronics")
        (field (name "CASE/PACKAGE") "LGA-16")
        (field (name "MANUFACTURER PART NUMBER") "LIS3DHTR")
        (field (name "HOUSE_PART_NUMBER") "LIS3DHTR")
      )
      (libsource (lib "lamp_controller") (part "LIS3DHTR"))
    )
    (comp (ref "U8")
      (value "Magnet Sensor")
      (footprint "SOT-23-6")
      (description "3-Axis Hall sensor, I2C, SOT-23-6")
      (fields
        (field (name "MANUFACTURER") "Texas Instruments")
        (field (name "PACKAGE") "SOT-23-6")
        (field (name "MANUFACTURER PART NUMBER") "TMAG5273A2QDBVR")
      )
      (libsource (lib "lamp_controller") (part "TMAG5273A2QDBVR"))
    )
    (comp (ref "Y1")
      (value "12MHz")
      (footprint "3225_crystal")
      (description "12 MHz, 10 ppm, 20 pF, 3225 Crystal")
      (fields
        (field (name "HOUSE_PART_NUMBER") "TAXM12M4RLBDDT2T")
        (field (name "ESR") "50Ω")
        (field (name "MANUFACTURER PART NUMBER") "TAXM12M4RLBDDT2T")
        (field (name "CASE/PACKAGE") "3225")
      )
      (libsource (lib "lamp_controller") (part "TAXM12M4RLBDDT2T"))
    )
  )
  (nets
    (net (code "1") (name "+3.3V") (class "Default")
      (node (ref "C10") (pin "2") (pinfunction "2_2") (pintype "passive"))
      (node (ref "C11") (pin "2") (pinfunction "2_2") (pintype "passive"))
      (node (ref "C12") (pin "2") (pinfunction "2_2") (pintype "passive"))
      (node (ref "C13") (pin "2") (pinfunction "2_2") (pintype "passive"))
      (node (ref "C14") (pin "2") (pinfunction "2_2") (pintype "passive"))
      (node (ref "C15") (pin "2") (pinfunction "2_2") (pintype "passive"))
      (node (ref "C16") (pin "2") (pinfunction "2_2") (pintype "passive"))
      (node (ref "C34") (pin "2") (pinfunction "2_2") (pintype "passive"))
      (node (ref "C35") (pin "2") (pinfunction "2_2") (pintype "passive"))
      (node (ref "C39") (pin "2") (pinfunction "2_2") (pintype "passive"))
      (node (ref "C40") (pin "2") (pinfunction "2_2") (pintype "passive"))
      (node (ref "C48") (pin "2") (pinfunction "2_2") (pintype "passive"))
      (node (ref "C49") (pin "2") (pinfunction "2_2") (pintype "passive"))
      (node (ref "C51") (pin "2") (pinfunction "2_2") (pintype "passive"))
      (node (ref "C54") (pin "2") (pinfunction "2_2") (pintype "passive"))
      (node (ref "C8") (pin "2") (pinfunction "2_2") (pintype "passive"))
      (node (ref "C9") (pin "2") (pinfunction "2_2") (pintype "passive"))
      (node (ref "J11") (pin "1") (pintype "passive"))
      (node (ref "J12") (pin "1") (pinfunction "LEDA_1") (pintype "passive"))
      (node (ref "J12") (pin "3") (pinfunction "VDD_3") (pintype "power_in"))
      (node (ref "J12") (pin "4") (pinfunction "VDDIO_4") (pintype "power_in"))
      (node (ref "J5") (pin "1") (pinfunction "VCC_1") (pintype "power_in"))
      (node (ref "M1") (pin "9") (pinfunction "VDD_9") (pintype "power_in"))
      (node (ref "M1") (pin "F4") (pinfunction "VDDH_F4") (pintype "power_in"))
      (node (ref "M2") (pin "3") (pinfunction "3V3_3") (pintype "power_in"))
      (node (ref "R12") (pin "2") (pinfunction "2_2") (pintype "passive"))
      (node (ref "R13") (pin "1") (pinfunction "1_1") (pintype "passive"))
      (node (ref "R3") (pin "1") (pinfunction "1_1") (pintype "passive"))
      (node (ref "R31") (pin "1") (pinfunction "1_1") (pintype "passive"))
      (node (ref "R32") (pin "1") (pinfunction "1_1") (pintype "passive"))
      (node (ref "R33") (pin "1") (pinfunction "1_1") (pintype "passive"))
      (node (ref "R34") (pin "1") (pinfunction "1_1") (pintype "passive"))
      (node (ref "R36") (pin "1") (pinfunction "1_1") (pintype "passive"))
      (node (ref "R44") (pin "2") (pinfunction "2_2") (pintype "passive"))
      (node (ref "R45") (pin "2") (pinfunction "2_2") (pintype "passive"))
      (node (ref "U2") (pin "8") (pinfunction "VCC_8") (pintype "power_in"))
      (node (ref "U3") (pin "1") (pinfunction "IOVDD_1") (pintype "power_in"))
      (node (ref "U3") (pin "10") (pinfunction "IOVDD_10") (pintype "power_in"))
      (node (ref "U3") (pin "22") (pinfunction "IOVDD_22") (pintype "power_in"))
      (node (ref "U3") (pin "33") (pinfunction "IOVDD_33") (pintype "power_in"))
      (node (ref "U3") (pin "42") (pinfunction "IOVDD_42") (pintype "power_in"))
      (node (ref "U3") (pin "43") (pinfunction "ADC_IOVDD_43") (pintype "power_in"))
      (node (ref "U3") (pin "44") (pinfunction "VREG_VIN_44") (pintype "power_in"))
      (node (ref "U3") (pin "48") (pinfunction "USB_VDD_48") (pintype "power_in"))
      (node (ref "U3") (pin "49") (pinfunction "IOVDD_49") (pintype "power_in"))
      (node (ref "U7") (pin "1") (pinfunction "VDDIO_1") (pintype "power_in"))
      (node (ref "U7") (pin "14") (pinfunction "VDD_14") (pintype "power_in"))
      (node (ref "U7") (pin "7") (pinfunction "SDO/SA0_7") (pintype "bidirectional"))
      (node (ref "U7") (pin "8") (pinfunction "CS_8") (pintype "input"))
      (node (ref "U8") (pin "4") (pinfunction "VCC_4") (pintype "power_in"))
    )
    (net (code "2") (name "+5V") (class "Default")
      (node (ref "J8") (pin "5") (pinfunction "VCC_5") (pintype "power_in"))
    )
    (net (code "3") (name "+12V_SWITCHED") (class "Default")
      (node (ref "J10") (pin "2") (pintype "passive"))
      (node (ref "J6") (pin "1") (pintype "passive"))
      (node (ref "J7") (pin "2") (pinfunction "VIN_2") (pintype "power_in"))
    )
    (net (code "4") (name "+24V") (class "Default") (node (ref "J2") (pin "1") (pintype "passive")))
    (net (code "5") (name "/+12V_ENABLE") (class "Default")
      (node (ref "U3") (pin "9") (pinfunction "GPIO7_9") (pintype "bidirectional"))
    )
    (net (code "6") (name "/+12V_VSENSE") (class "Default")
      (node (ref "U3") (pin "39") (pinfunction "GPIO27/ADC1_39") (pintype "bidirectional"))
    )
    (net (code "7") (name "/+24V_ENABLE") (class "Default")
      (node (ref "U3") (pin "18") (pinfunction "GPIO15_18") (pintype "bidirectional"))
    )
    (net (code "8") (name "/+24V_VSENSE") (class "Default")
      (node (ref "U3") (pin "41") (pinfunction "GPIO29/ADC3_41") (pintype "bidirectional"))
    )
    (net (code "9") (name "/CENTER") (class "Default")
      (node (ref "C44") (pin "2") (pinfunction "2_2") (pintype "passive"))
      (node (ref "R55") (pin "1") (pinfunction "1_1") (pintype "passive"))
      (node (ref "SW3") (pin "3") (pinfunction "3_3") (pintype "passive"))
      (node (ref "SW3") (pin "4") (pinfunction "4_4") (pintype "passive"))
      (node (ref "U3") (pin "28") (pinfunction "GPIO17_28") (pintype "bidirectional"))
    )
    (net (code "10") (name "/DOWN") (class "Default")
      (node (ref "C53") (pin "2") (pinfunction "2_2") (pintype "passive"))
      (node (ref "SW8") (pin "3") (pinfunction "3_3") (pintype "passive"))
      (node (ref "SW8") (pin "4") (pinfunction "4_4") (pintype "passive"))
      (node (ref "U3") (pin "35") (pinfunction "GPIO23_35") (pintype "bidirectional"))
    )
    (net (code "11") (name "/ESP32_BOOT") (class "Default")
      (node (ref "J11") (pin "5") (pintype "passive"))
      (node (ref "M2") (pin "23") (pinfunction "GPIO9_23") (pintype "bidirectional"))
      (node (ref "R55") (pin "2") (pinfunction "2_2") (pintype "passive"))
      (node (ref "SW5") (pin "1") (pinfunction "1_1") (pintype "passive"))
      (node (ref "SW5") (pin "2") (pinfunction "2_2") (pintype "passive"))
    )
    (net (code "12") (name "/FAN_PWM") (class "Default")
      (node (ref "R23") (pin "1") (pinfunction "1_1") (pintype "passive"))
      (node (ref "U3") (pin "13") (pinfunction "GPIO10_13") (pintype "bidirectional"))
    )
    (net (code "13") (name "/FAN_TACH") (class "Default")
      (node (ref "J7") (pin "3") (pinfunction "TACH_3") (pintype "open_collector"))
      (node (ref "R33") (pin "2") (pinfunction "2_2") (pintype "passive"))
      (node (ref "TP30") (pin "1") (pinfunction "1_1") (pintype "passive"))
      (node (ref "U3") (pin "14") (pinfunction "GPIO11_14") (pintype "bidirectional"))
    )
    (net (code "14") (name "/LAMP_ENABLE") (class "Default")
      (node (ref "R7") (pin "1") (pinfunction "1_1") (pintype "passive"))
      (node (ref "TP7") (pin "1") (pinfunction "1_1") (pintype "passive"))
      (node (ref "U3") (pin "17") (pinfunction "GPIO14_17") (pintype "bidirectional"))
    )
    (net (code "15") (name "/LAMP_PWM") (class "Default")
      (node (ref "R22") (pin "1") (pinfunction "1_1") (pintype "passive"))
      (node (ref "U3") (pin "16") (pinfunction "GPIO13_16") (pintype "bidirectional"))
    )
    (net (code "16") (name "/LAMP_REMOTE") (class "Default")
      (node (ref "J2") (pin "2") (pintype "passive"))
      (node (ref "J6") (pin "2") (pintype "passive"))
      (node (ref "Q1") (pin "3") (pinfunction "D_3") (pintype "passive"))
    )
    (net (code "17") (name "/LAMP_STATUS") (class "Default")
      (node (ref "J2") (pin "3") (pintype "passive"))
      (node (ref "J6") (pin "4") (pintype "passive"))
      (node (ref "TP13") (pin "1") (pinfunction "1_1") (pintype "passive"))
      (node (ref "U3") (pin "15") (pinfunction "GPIO12_15") (pintype "bidirectional"))
    )
    (net (code "18") (name "/LCD_BACKLIGHT") (class "Default")
      (node (ref "R52") (pin "1") (pinfunction "1_1") (pintype "passive"))
      (node (ref "U3") (pin "37") (pinfunction "GPIO25_37") (pintype "bidirectional"))
    )
    (net (code "19") (name "/LCD_CS") (class "Default")
      (node (ref "J12") (pin "8") (pinfunction "CS_8") (pintype "input"))
      (node (ref "TP35") (pin "1") (pinfunction "1_1") (pintype "passive"))
      (node (ref "U3") (pin "36") (pinfunction "GPIO24_36") (pintype "bidirectional"))
    )
    (net (code "20") (name "/LCD_D{slash}C") (class "Default")
      (node (ref "J12") (pin "10") (pinfunction "D/C_10") (pintype "input"))
      (node (ref "TP33") (pin "1") (pinfunction "1_1") (pintype "passive"))
      (node (ref "U3") (pin "34") (pinfunction "GPIO22_34") (pintype "bidirectional"))
    )
    (net (code "21") (name "/LCD_RESET") (class "Default")
      (node (ref "J12") (pin "7") (pinfunction "RESET_7") (pintype "input"))
      (node (ref "TP36") (pin "1") (pinfunction "1_1") (pintype "passive"))
      (node (ref "U3") (pin "32") (pinfunction "GPIO21_32") (pintype "bidirectional"))
    )
    (net (code "22") (name "/LCD_SCLK") (class "Default")
      (node (ref "J12") (pin "9") (pinfunction "SCLK_9") (pintype "input"))
      (node (ref "TP34") (pin "1") (pinfunction "1_1") (pintype "passive"))
      (node (ref "U3") (pin "29") (pinfunction "GPIO18_29") (pintype "bidirectional"))
    )
    (net (code "23") (name "/LCD_SDA") (class "Default")
      (node (ref "J12") (pin "11") (pinfunction "SDA_11") (pintype "bidirectional"))
      (node (ref "TP32") (pin "1") (pinfunction "1_1") (pintype "passive"))
      (node (ref "U3") (pin "30") (pinfunction "GPIO19_30") (pintype "bidirectional"))
    )
    (net (code "24") (name "/LEFT") (class "Default")
      (node (ref "C43") (pin "2") (pinfunction "2_2") (pintype "passive"))
      (node (ref "SW2") (pin "3") (pinfunction "3_3") (pintype "passive"))
      (node (ref "SW2") (pin "4") (pinfunction "4_4") (pintype "passive"))
      (node (ref "U3") (pin "27") (pinfunction "GPIO16_27") (pintype "bidirectional"))
    )
    (net (code "25") (name "/MMWAVE_RX") (class "Default")
      (node (ref "R38") (pin "1") (pinfunction "1_1") (pintype "passive"))
      (node (ref "U3") (pin "2") (pinfunction "GPIO0_2") (pintype "bidirectional"))
    )
    (net (code "26") (name "/MMWAVE_TX") (class "Default")
      (node (ref "R37") (pin "1") (pinfunction "1_1") (pintype "passive"))
      (node (ref "U3") (pin "3") (pinfunction "GPIO1_3") (pintype "bidirectional"))
    )
    (net (code "27") (name "/QSPI_SCLK") (class "Default")
      (node (ref "U2") (pin "6") (pinfunction "CLK_6") (pintype "input"))
      (node (ref "U3") (pin "52") (pinfunction "QSPI_SCLK_52") (pintype "output"))
    )
    (net (code "28") (name "/QSPI_SDO0") (class "Default")
      (node (ref "U2") (pin "5") (pinfunction "DI_(IO0)_5") (pintype "bidirectional"))
      (node (ref "U3") (pin "53") (pinfunction "QSPI_SD0_53") (pintype "bidirectional"))
    )
    (net (code "29") (name "/QSPI_SDO1") (class "Default")
      (node (ref "U2") (pin "2") (pinfunction "DO_(IO1)_2") (pintype "bidirectional"))
      (node (ref "U3") (pin "55") (pinfunction "QSPI_SD1_55") (pintype "bidirectional"))
    )
    (net (code "30") (name "/QSPI_SDO2") (class "Default")
      (node (ref "U2") (pin "3") (pinfunction "~{WP}_(IO2)_3") (pintype "bidirectional"))
      (node (ref "U3") (pin "54") (pinfunction "QSPI_SD2_54") (pintype "bidirectional"))
    )
    (net (code "31") (name "/QSPI_SDO3") (class "Default")
      (node (ref "U2") (pin "7") (pinfunction "~{HOLD}_(IO3)_7") (pintype "bidirectional"))
      (node (ref "U3") (pin "51") (pinfunction "QSPI_SD3_51") (pintype "bidirectional"))
    )
    (net (code "32") (name "/QSPI_SS") (class "Default")
      (node (ref "R12") (pin "1") (pinfunction "1_1") (pintype "passive"))
      (node (ref "R24") (pin "1") (pinfunction "1_1") (pintype "passive"))
      (node (ref "U2") (pin "1") (pinfunction "~{CS}_1") (pintype "input"))
      (node (ref "U3") (pin "56") (pinfunction "QSPI_SSn_56") (pintype "output"))
    )
    (net (code "33") (name "/RADIO_ENABLE") (class "Default")
      (node (ref "C50") (pin "2") (pinfunction "2_2") (pintype "passive"))
      (node (ref "J11") (pin "6") (pintype "passive"))
      (node (ref "J5") (pin "3") (pinfunction "~{RESET}_3") (pintype "bidirectional"))
      (node (ref "M1") (pin "14") (pinfunction "/RESET_14") (pintype "bidirectional"))
      (node (ref "M2") (pin "8") (pinfunction "EN_8") (pintype "input"))
      (node (ref "R45") (pin "1") (pinfunction "1_1") (pintype "passive"))
      (node (ref "R46") (pin "2") (pinfunction "2_2") (pintype "passive"))
    )
    (net (code "34") (name "/RADIO_RX") (class "Default")
      (node (ref "J11") (pin "3") (pintype "passive"))
      (node (ref "M1") (pin "6") (pinfunction "P0.05/AIN1_6") (pintype "bidirectional"))
      (node (ref "M2") (pin "30") (pinfunction "U0RXD/GPIO17/FSPICS1_30") (pintype "bidirectional"))
      (node (ref "R47") (pin "2") (pinfunction "2_2") (pintype "passive"))
    )
    (net (code "35") (name "/RADIO_TX") (class "Default")
      (node (ref "J11") (pin "4") (pintype "passive"))
      (node (ref "M1") (pin "5") (pinfunction "P0.04/AIN0_5") (pintype "bidirectional"))
      (node (ref "M2") (pin "31") (pinfunction "U0TXD/GPIO16/FSPICS0_31") (pintype "bidirectional"))
      (node (ref "R48") (pin "2") (pinfunction "2_2") (pintype "passive"))
    )
    (net (code "36") (name "/RIGHT") (class "Default")
      (node (ref "C52") (pin "2") (pinfunction "2_2") (pintype "passive"))
      (node (ref "SW7") (pin "3") (pinfunction "3_3") (pintype "passive"))
      (node (ref "SW7") (pin "4") (pinfunction "4_4") (pintype "passive"))
      (node (ref "U3") (pin "31") (pinfunction "GPIO20_31") (pintype "bidirectional"))
    )
    (net (code "37") (name "/RUN") (class "Default")
      (node (ref "R36") (pin "2") (pinfunction "2_2") (pintype "passive"))
      (node (ref "SW6") (pin "3") (pinfunction "3_3") (pintype "passive"))
      (node (ref "SW6") (pin "4") (pinfunction "4_4") (pintype "passive"))
      (node (ref "U3") (pin "26") (pinfunction "RUN_26") (pintype "input"))
    )
    (net (code "38") (name "/SCL") (class "Default")
      (node (ref "R31") (pin "2") (pinfunction "2_2") (pintype "passive"))
      (node (ref "U3") (pin "5") (pinfunction "GPIO3_5") (pintype "bidirectional"))
      (node (ref "U7") (pin "4") (pinfunction "SCL/SPC_4") (pintype "input"))
      (node (ref "U8") (pin "1") (pinfunction "SCL_1") (pintype "bidirectional"))
    )
    (net (code "39") (name "/SDA") (class "Default")
      (node (ref "R32") (pin "2") (pinfunction "2_2") (pintype "passive"))
      (node (ref "U3") (pin "4") (pinfunction "GPIO2_4") (pintype "bidirectional"))
      (node (ref "U7") (pin "6") (pinfunction "SDA/SDI/SDO_6") (pintype "bidirectional"))
      (node (ref "U8") (pin "6") (pinfunction "SDA_6") (pintype "bidirectional"))
    )
    (net (code "40") (name "/SWCLK") (class "Default")
      (node (ref "J4") (pin "4") (pinfunction "SWCLK_4") (pintype "bidirectional"))
      (node (ref "U3") (pin "24") (pinfunction "SWCLK_24") (pintype "bidirectional"))
    )
    (net (code "41") (name "/SWDIO") (class "Default")
      (node (ref "J4") (pin "2") (pinfunction "SWDIO_2") (pintype "bidirectional"))
      (node (ref "U3") (pin "25") (pinfunction "SWDIO_25") (pintype "bidirectional"))
    )
    (net (code "42") (name "/UART_RX") (class "Default")
      (node (ref "R43") (pin "1") (pinfunction "1_1") (pintype "passive"))
      (node (ref "U3") (pin "11") (pinfunction "GPIO8_11") (pintype "bidirectional"))
    )
    (net (code "43") (name "/UART_TX") (class "Default")
      (node (ref "R42") (pin "1") (pinfunction "1_1") (pintype "passive"))
      (node (ref "U3") (pin "12") (pinfunction "GPIO9_12") (pintype "bidirectional"))
    )
    (net (code "44") (name "/UP") (class "Default")
      (node (ref "C42") (pin "2") (pinfunction "2_2") (pintype "passive"))
      (node (ref "SW1") (pin "3") (pinfunction "3_3") (pintype "passive"))
      (node (ref "SW1") (pin "4") (pinfunction "4_4") (pintype "passive"))
      (node (ref "U3") (pin "40") (pinfunction "GPIO28/ADC2_40") (pintype "bidirectional"))
    )
    (net (code "45") (name "/USB0_D+") (class "Default")
      (node (ref "R25") (pin "2") (pinfunction "2_2") (pintype "passive"))
    )
    (net (code "46") (name "/USB0_D-") (class "Default")
      (node (ref "R26") (pin "2") (pinfunction "2_2") (pintype "passive"))
    )
    (net (code "47") (name "/USB1_D+") (class "Default")
      (node (ref "R25") (pin "1") (pinfunction "1_1") (pintype "passive"))
      (node (ref "U3") (pin "47") (pinfunction "USB_D+_47") (pintype "bidirectional"))
    )
    (net (code "48") (name "/USB1_D-") (class "Default")
      (node (ref "R26") (pin "1") (pinfunction "1_1") (pintype "passive"))
      (node (ref "U3") (pin "46") (pinfunction "USB_D-_46") (pintype "bidirectional"))
    )
    (net (code "49") (name "/VBUS_VSENSE") (class "Default")
      (node (ref "U3") (pin "38") (pinfunction "GPIO26/ADC0_38") (pintype "bidirectional"))
    )
    (net (code "50") (name "/nRF_SWCLK") (class "Default")
      (node (ref "J5") (pin "4") (pinfunction "SWCLK_4") (pintype "bidirectional"))
      (node (ref "M1") (pin "15") (pinfunction "SWDCLK_15") (pintype "input"))
    )
    (net (code "51") (name "/nRF_SWDIO") (class "Default")
      (node (ref "J5") (pin "2") (pinfunction "SWDIO_2") (pintype "bidirectional"))
      (node (ref "M1") (pin "16") (pinfunction "SWDIO_16") (pintype "bidirectional"))
    )
    (net (code "52") (name "GND") (class "Default")
      (node (ref "C10") (pin "1") (pinfunction "1_1") (pintype "passive"))
      (node (ref "C11") (pin "1") (pinfunction "1_1") (pintype "passive"))
      (node (ref "C12") (pin "1") (pinfunction "1_1") (pintype "passive"))
      (node (ref "C13") (pin "1") (pinfunction "1_1") (pintype "passive"))
      (node (ref "C14") (pin "1") (pinfunction "1_1") (pintype "passive"))
      (node (ref "C15") (pin "1") (pinfunction "1_1") (pintype "passive"))
      (node (ref "C16") (pin "1") (pinfunction "1_1") (pintype "passive"))
      (node (ref "C17") (pin "1") (pinfunction "1_1") (pintype "passive"))
      (node (ref "C18") (pin "1") (pinfunction "1_1") (pintype "passive"))
      (node (ref "C19") (pin "1") (pinfunction "1_1") (pintype "passive"))
      (node (ref "C20") (pin "1") (pinfunction "1_1") (pintype "passive"))
      (node (ref "C21") (pin "1") (pinfunction "1_1") (pintype "passive"))
      (node (ref "C34") (pin "1") (pinfunction "1_1") (pintype "passive"))
      (node (ref "C35") (pin "1") (pinfunction "1_1") (pintype "passive"))
      (node (ref "C36") (pin "1") (pinfunction "1_1") (pintype "passive"))
      (node (ref "C39") (pin "1") (pinfunction "1_1") (pintype "passive"))
      (node (ref "C40") (pin "1") (pinfunction "1_1") (pintype "passive"))
      (node (ref "C41") (pin "1") (pinfunction "1_1") (pintype "passive"))
      (node (ref "C42") (pin "1") (pinfunction "1_1") (pintype "passive"))
      (node (ref "C43") (pin "1") (pinfunction "1_1") (pintype "passive"))
      (node (ref "C44") (pin "1") (pinfunction "1_1") (pintype "passive"))
      (node (ref "C48") (pin "1") (pinfunction "1_1") (pintype "passive"))
      (node (ref "C49") (pin "1") (pinfunction "1_1") (pintype "passive"))
      (node (ref "C50") (pin "1") (pinfunction "1_1") (pintype "passive"))
      (node (ref "C51") (pin "1") (pinfunction "1_1") (pintype "passive"))
      (node (ref "C52") (pin "1") (pinfunction "1_1") (pintype "passive"))
      (node (ref "C53") (pin "1") (pinfunction "1_1") (pintype "passive"))
      (node (ref "C54") (pin "1") (pinfunction "1_1") (pintype "passive"))
      (node (ref "C8") (pin "1") (pinfunction "1_1") (pintype "passive"))
      (node (ref "C9") (pin "1") (pinfunction "1_1") (pintype "passive"))
      (node (ref "J11") (pin "2") (pintype "passive"))
      (node (ref "J12") (pin "13") (pinfunction "GND_13") (pintype "power_in"))
      (node (ref "J12") (pin "14") (pinfunction "GND_14") (pintype "power_in"))
      (node (ref "J12") (pin "15") (pinfunction "GND_15") (pintype "power_in"))
      (node (ref "J12") (pin "5") (pinfunction "GND_5") (pintype "power_in"))
      (node (ref "J12") (pin "6") (pinfunction "GND_6") (pintype "power_in"))
      (node (ref "J12") (pin "MP") (pintype "passive"))
      (node (ref "J2") (pin "4") (pintype "passive"))
      (node (ref "J4") (pin "5") (pinfunction "GND_5") (pintype "power_in"))
      (node (ref "J5") (pin "5") (pinfunction "GND_5") (pintype "power_in"))
      (node (ref "J6") (pin "5") (pintype "passive"))
      (node (ref "J7") (pin "1") (pinfunction "GND_1") (pintype "power_in"))
      (node (ref "J8") (pin "4") (pinfunction "GND_4") (pintype "power_in"))
      (node (ref "J9") (pin "3") (pintype "passive"))
      (node (ref "M1") (pin "10") (pinfunction "VSS_10") (pintype "power_in"))
      (node (ref "M1") (pin "A0") (pinfunction "VSS_A0") (pintype "power_in"))
      (node (ref "M1") (pin "B0") (pinfunction "VSS_B0") (pintype "power_in"))
      (node (ref "M1") (pin "C0") (pinfunction "VSS_C0") (pintype "power_in"))
      (node (ref "M1") (pin "D0") (pinfunction "VSS_D0") (pintype "power_in"))
      (node (ref "M1") (pin "H0") (pinfunction "VSS_H0") (pintype "power_in"))
      (node (ref "M1") (pin "H1") (pinfunction "VSS_H1") (pintype "power_in"))
      (node (ref "M1") (pin "H2") (pinfunction "VSS_H2") (pintype "power_in"))
      (node (ref "M1") (pin "H3") (pinfunction "VSS_H3") (pintype "power_in"))
      (node (ref "M2") (pin "1") (pinfunction "GND_1") (pintype "power_in"))
      (node (ref "M2") (pin "11") (pinfunction "GND_11") (pintype "power_in"))
      (node (ref "M2") (pin "14") (pinfunction "GND_14") (pintype "power_in"))
      (node (ref "M2") (pin "2") (pinfunction "GND_2") (pintype "power_in"))
      (node (ref "M2") (pin "36") (pinfunction "GND_36") (pintype "power_in"))
      (node (ref "M2") (pin "37") (pinfunction "GND_37") (pintype "power_in"))
      (node (ref "M2") (pin "38") (pinfunction "GND_38") (pintype "power_in"))
      (node (ref "M2") (pin "39") (pinfunction "GND_39") (pintype "power_in"))
      (node (ref "M2") (pin "40") (pinfunction "GND_40") (pintype "power_in"))
      (node (ref "M2") (pin "41") (pinfunction "GND_41") (pintype "power_in"))
      (node (ref "M2") (pin "42") (pinfunction "GND_42") (pintype "power_in"))
      (node (ref "M2") (pin "43") (pinfunction "GND_43") (pintype "power_in"))
      (node (ref "M2") (pin "44") (pinfunction "GND_44") (pintype "power_in"))
      (node (ref "M2") (pin "45") (pinfunction "GND_45") (pintype "power_in"))
      (node (ref "M2") (pin "46") (pinfunction "GND_46") (pintype "power_in"))
      (node (ref "M2") (pin "47") (pinfunction "GND_47") (pintype "power_in"))
      (node (ref "M2") (pin "48") (pinfunction "GND_48") (pintype "power_in"))
      (node (ref "M2") (pin "49") (pinfunction "GND_49") (pintype "power_in"))
      (node (ref "M2") (pin "50") (pinfunction "GND_50") (pintype "power_in"))
      (node (ref "M2") (pin "51") (pinfunction "GND_51") (pintype "power_in"))
      (node (ref "M2") (pin "52") (pinfunction "GND_52") (pintype "power_in"))
      (node (ref "M2") (pin "53") (pinfunction "GND_53") (pintype "power_in"))
      (node (ref "Q1") (pin "2") (pinfunction "S_2") (pintype "passive"))
      (node (ref "Q5") (pin "2") (pinfunction "S_2") (pintype "passive"))
      (node (ref "Q6") (pin "2") (pinfunction "S_2") (pintype "passive"))
      (node (ref "R35") (pin "2") (pinfunction "2_2") (pintype "passive"))
      (node (ref "R40") (pin "2") (pinfunction "2_2") (pintype "passive"))
      (node (ref "R53") (pin "2") (pinfunction "2_2") (pintype "passive"))
      (node (ref "SW1") (pin "1") (pinfunction "1_1") (pintype "passive"))
      (node (ref "SW1") (pin "2") (pinfunction "2_2") (pintype "passive"))
      (node (ref "SW2") (pin "1") (pinfunction "1_1") (pintype "passive"))
      (node (ref "SW2") (pin "2") (pinfunction "2_2") (pintype "passive"))
      (node (ref "SW3") (pin "1") (pinfunction "1_1") (pintype "passive"))
      (node (ref "SW3") (pin "2") (pinfunction "2_2") (pintype "passive"))
      (node (ref "SW4") (pin "3") (pinfunction "3_3") (pintype "passive"))
      (node (ref "SW4") (pin "4") (pinfunction "4_4") (pintype "passive"))
      (node (ref "SW5") (pin "3") (pinfunction "3_3") (pintype "passive"))
      (node (ref "SW5") (pin "4") (pinfunction "4_4") (pintype "passive"))
      (node (ref "SW6") (pin "1") (pinfunction "1_1") (pintype "passive"))
      (node (ref "SW6") (pin "2") (pinfunction "2_2") (pintype "passive"))
      (node (ref "SW7") (pin "1") (pinfunction "1_1") (pintype "passive"))
      (node (ref "SW7") (pin "2") (pinfunction "2_2") (pintype "passive"))
      (node (ref "SW8") (pin "1") (pinfunction "1_1") (pintype "passive"))
      (node (ref "SW8") (pin "2") (pinfunction "2_2") (pintype "passive"))
      (node (ref "TP10") (pin "1") (pinfunction "1_1") (pintype "passive"))
      (node (ref "TP38") (pin "1") (pinfunction "1_1") (pintype "passive"))
      (node (ref "U2") (pin "4") (pinfunction "GND_4") (pintype "power_in"))
      (node (ref "U3") (pin "19") (pinfunction "TESTEN_19") (pintype "bidirectional"))
      (node (ref "U3") (pin "EP") (pinfunction "GND_EP") (pintype "power_in"))
      (node (ref "U7") (pin "10") (pinfunction "RES_10") (pintype "power_in"))
      (node (ref "U7") (pin "12") (pinfunction "GND_12") (pintype "power_in"))
      (node (ref "U7") (pin "5") (pinfunction "GND_5") (pintype "power_in"))
      (node (ref "U8") (pin "2") (pinfunction "GND_2") (pintype "power_in"))
      (node (ref "U8") (pin "3") (pinfunction "GND_(TEST)_3") (pintype "input"))
      (node (ref "Y1") (pin "2") (pinfunction "GND_2") (pintype "power_in"))
      (node (ref "Y1") (pin "4") (pinfunction "GND_4") (pintype "power_in"))
    )
    (net (code "53") (name "Net-(C21-Pad2)") (class "Default")
      (node (ref "C21") (pin "2") (pinfunction "2_2") (pintype "passive"))
      (node (ref "R15") (pin "1") (pinfunction "1_1") (pintype "passive"))
      (node (ref "Y1") (pin "3") (pinfunction "OSC_3") (pintype "passive"))
    )
    (net (code "54") (name "Net-(C36-Pad2)") (class "Default")
      (node (ref "C36") (pin "2") (pinfunction "2_2") (pintype "passive"))
      (node (ref "J6") (pin "3") (pintype "passive"))
      (node (ref "R22") (pin "2") (pinfunction "2_2") (pintype "passive"))
      (node (ref "TP23") (pin "1") (pinfunction "1_1") (pintype "passive"))
    )
    (net (code "55") (name "Net-(J7-PWM)") (class "Default")
      (node (ref "J7") (pin "4") (pinfunction "PWM_4") (pintype "input"))
      (node (ref "Q5") (pin "1") (pinfunction "G_1") (pintype "passive"))
      (node (ref "R23") (pin "2") (pinfunction "2_2") (pintype "passive"))
      (node (ref "R34") (pin "2") (pinfunction "2_2") (pintype "passive"))
      (node (ref "R35") (pin "1") (pinfunction "1_1") (pintype "passive"))
      (node (ref "TP31") (pin "1") (pinfunction "1_1") (pintype "passive"))
    )
    (net (code "56") (name "Net-(J8-OUT)") (class "Default")
      (node (ref "J8") (pin "3") (pinfunction "OUT_3") (pintype "output"))
      (node (ref "TP21") (pin "1") (pinfunction "1_1") (pintype "passive"))
    )
    (net (code "57") (name "Net-(J8-RX)") (class "Default")
      (node (ref "J8") (pin "2") (pinfunction "RX_2") (pintype "input"))
      (node (ref "R38") (pin "2") (pinfunction "2_2") (pintype "passive"))
    )
    (net (code "58") (name "Net-(J8-TX)") (class "Default")
      (node (ref "J8") (pin "1") (pinfunction "TX_1") (pintype "output"))
      (node (ref "R37") (pin "2") (pinfunction "2_2") (pintype "passive"))
    )
    (net (code "59") (name "Net-(J9-Pad1)") (class "Default")
      (node (ref "J9") (pin "1") (pintype "passive"))
      (node (ref "R42") (pin "2") (pinfunction "2_2") (pintype "passive"))
    )
    (net (code "60") (name "Net-(J9-Pad2)") (class "Default")
      (node (ref "J9") (pin "2") (pintype "passive"))
      (node (ref "R43") (pin "2") (pinfunction "2_2") (pintype "passive"))
    )
    (net (code "61") (name "Net-(J12-LEDK)") (class "Default")
      (node (ref "J12") (pin "2") (pinfunction "LEDK_2") (pintype "passive"))
      (node (ref "R49") (pin "1") (pinfunction "1_1") (pintype "passive"))
      (node (ref "R50") (pin "1") (pinfunction "1_1") (pintype "passive"))
      (node (ref "R51") (pin "1") (pinfunction "1_1") (pintype "passive"))
      (node (ref "TP37") (pin "1") (pinfunction "1_1") (pintype "passive"))
    )
    (net (code "62") (name "Net-(M1-P1.04)") (class "Default")
      (node (ref "M1") (pin "E0") (pinfunction "P1.04_E0") (pintype "bidirectional"))
      (node (ref "TP15") (pin "1") (pinfunction "1_1") (pintype "passive"))
    )
    (net (code "63") (name "Net-(M1-P1.06)") (class "Default")
      (node (ref "M1") (pin "E2") (pinfunction "P1.06_E2") (pintype "bidirectional"))
      (node (ref "TP17") (pin "1") (pinfunction "1_1") (pintype "passive"))
    )
    (net (code "64") (name "Net-(M1-P1.09)") (class "Default")
      (node (ref "M1") (pin "Z0") (pinfunction "P1.09_Z0") (pintype "bidirectional"))
      (node (ref "TP18") (pin "1") (pinfunction "1_1") (pintype "passive"))
    )
    (net (code "65") (name "Net-(M1-VBAT)") (class "Default")
      (node (ref "C41") (pin "2") (pinfunction "2_2") (pintype "passive"))
      (node (ref "M1") (pin "17") (pinfunction "VBAT_17") (pintype "power_in"))
      (node (ref "R13") (pin "2") (pinfunction "2_2") (pintype "passive"))
      (node (ref "TP12") (pin "1") (pinfunction "1_1") (pintype "passive"))
    )
    (net (code "66") (name "Net-(M2-GPIO0{slash}XTAL_32K_P{slash}LP_GPIO0{slash}LP_UART_DTRN{slash}ADC1_CH0)") (class "Default")
      (node (ref "M2") (pin "12") (pinfunction "GPIO0/XTAL_32K_P/LP_GPIO0/LP_UART_DTRN/ADC1_CH0_12") (pintype "bidirectional"))
      (node (ref "TP5") (pin "1") (pinfunction "1_1") (pintype "passive"))
    )
    (net (code "67") (name "Net-(M2-GPIO2{slash}LP_GPIO2{slash}LP_UART_RTSN{slash}ADC1_CH2{slash}FSPIQ)") (class "Default")
      (node (ref "M2") (pin "5") (pinfunction "GPIO2/LP_GPIO2/LP_UART_RTSN/ADC1_CH2/FSPIQ_5") (pintype "bidirectional"))
      (node (ref "TP14") (pin "1") (pinfunction "1_1") (pintype "passive"))
    )
    (net (code "68") (name "Net-(M2-GPIO3{slash}LP_GPIO3{slash}LP_UART_CTSN{slash}ADC1_CH3)") (class "Default")
      (node (ref "M2") (pin "6") (pinfunction "GPIO3/LP_GPIO3/LP_UART_CTSN/ADC1_CH3_6") (pintype "bidirectional"))
      (node (ref "TP16") (pin "1") (pinfunction "1_1") (pintype "passive"))
    )
    (net (code "69") (name "Net-(M2-GPIO8)") (class "Default")
      (node (ref "M2") (pin "22") (pinfunction "GPIO8_22") (pintype "bidirectional"))
      (node (ref "R44") (pin "1") (pinfunction "1_1") (pintype "passive"))
    )
    (net (code "70") (name "Net-(Q1-G)") (class "Default")
      (node (ref "Q1") (pin "1") (pinfunction "G_1") (pintype "passive"))
      (node (ref "R3") (pin "2") (pinfunction "2_2") (pintype "passive"))
      (node (ref "R40") (pin "1") (pinfunction "1_1") (pintype "passive"))
      (node (ref "R7") (pin "2") (pinfunction "2_2") (pintype "passive"))
    )
    (net (code "71") (name "Net-(Q5-D)") (class "Default")
      (node (ref "J10") (pin "1") (pintype "passive"))
      (node (ref "Q5") (pin "3") (pinfunction "D_3") (pintype "passive"))
    )
    (net (code "72") (name "Net-(Q6-D)") (class "Default")
      (node (ref "Q6") (pin "3") (pinfunction "D_3") (pintype "passive"))
      (node (ref "R49") (pin "2") (pinfunction "2_2") (pintype "passive"))
      (node (ref "R50") (pin "2") (pinfunction "2_2") (pintype "passive"))
      (node (ref "R51") (pin "2") (pinfunction "2_2") (pintype "passive"))
    )
    (net (code "73") (name "Net-(Q6-G)") (class "Default")
      (node (ref "Q6") (pin "1") (pinfunction "G_1") (pintype "passive"))
      (node (ref "R52") (pin "2") (pinfunction "2_2") (pintype "passive"))
      (node (ref "R53") (pin "1") (pinfunction "1_1") (pintype "passive"))
      (node (ref "TP43") (pin "1") (pinfunction "1_1") (pintype "passive"))
    )
    (net (code "74") (name "Net-(R24-Pad2)") (class "Default")
      (node (ref "R24") (pin "2") (pinfunction "2_2") (pintype "passive"))
      (node (ref "SW4") (pin "1") (pinfunction "1_1") (pintype "passive"))
      (node (ref "SW4") (pin "2") (pinfunction "2_2") (pintype "passive"))
    )
    (net (code "75") (name "Net-(U3-GPIO4)") (class "Default")
      (node (ref "R47") (pin "1") (pinfunction "1_1") (pintype "passive"))
      (node (ref "U3") (pin "6") (pinfunction "GPIO4_6") (pintype "bidirectional"))
    )
    (net (code "76") (name "Net-(U3-GPIO5)") (class "Default")
      (node (ref "R48") (pin "1") (pinfunction "1_1") (pintype "passive"))
      (node (ref "U3") (pin "7") (pinfunction "GPIO5_7") (pintype "bidirectional"))
    )
    (net (code "77") (name "Net-(U3-GPIO6)") (class "Default")
      (node (ref "R46") (pin "1") (pinfunction "1_1") (pintype "passive"))
      (node (ref "U3") (pin "8") (pinfunction "GPIO6_8") (pintype "bidirectional"))
    )
    (net (code "78") (name "Net-(U3-VREG_VOUT)") (class "Default")
      (node (ref "C17") (pin "2") (pinfunction "2_2") (pintype "passive"))
      (node (ref "C18") (pin "2") (pinfunction "2_2") (pintype "passive"))
      (node (ref "C19") (pin "2") (pinfunction "2_2") (pintype "passive"))
      (node (ref "U3") (pin "23") (pinfunction "DVDD_23") (pintype "power_in"))
      (node (ref "U3") (pin "45") (pinfunction "VREG_VOUT_45") (pintype "power_in"))
      (node (ref "U3") (pin "50") (pinfunction "DVDD_50") (pintype "power_in"))
    )
    (net (code "79") (name "Net-(U3-XIN)") (class "Default")
      (node (ref "C20") (pin "2") (pinfunction "2_2") (pintype "passive"))
      (node (ref "U3") (pin "20") (pinfunction "XIN_20") (pintype "input"))
      (node (ref "Y1") (pin "1") (pinfunction "OSC_1") (pintype "passive"))
    )
    (net (code "80") (name "Net-(U3-XOUT)") (class "Default")
      (node (ref "R15") (pin "2") (pinfunction "2_2") (pintype "passive"))
      (node (ref "U3") (pin "21") (pinfunction "XOUT_21") (pintype "output"))
    )
    (net (code "81") (name "unconnected-(J4-SWO-Pad6)") (class "Default")
      (node (ref "J4") (pin "6") (pinfunction "SWO_6") (pintype "bidirectional+no_connect"))
    )
    (net (code "82") (name "unconnected-(J4-VCC-Pad1)") (class "Default")
      (node (ref "J4") (pin "1") (pinfunction "VCC_1") (pintype "power_in+no_connect"))
    )
    (net (code "83") (name "unconnected-(J4-~{RESET}-Pad3)") (class "Default")
      (node (ref "J4") (pin "3") (pinfunction "~{RESET}_3") (pintype "bidirectional+no_connect"))
    )
    (net (code "84") (name "unconnected-(J5-SWO-Pad6)") (class "Default")
      (node (ref "J5") (pin "6") (pinfunction "SWO_6") (pintype "bidirectional+no_connect"))
    )
    (net (code "85") (name "unconnected-(J12-TE-Pad12)") (class "Default")
      (node (ref "J12") (pin "12") (pinfunction "TE_12") (pintype "output+no_connect"))
    )
    (net (code "86") (name "unconnected-(M1-D+-PadE4)") (class "Default")
      (node (ref "M1") (pin "E4") (pinfunction "D+_E4") (pintype "bidirectional+no_connect"))
    )
    (net (code "87") (name "unconnected-(M1-D--PadE5)") (class "Default")
      (node (ref "M1") (pin "E5") (pinfunction "D-_E5") (pintype "bidirectional+no_connect"))
    )
    (net (code "88") (name "unconnected-(M1-NC-Pad3)") (class "Default")
      (node (ref "M1") (pin "3") (pinfunction "NC_3") (pintype "passive+no_connect"))
    )
    (net (code "89") (name "unconnected-(M1-NC-Pad4)") (class "Default")
      (node (ref "M1") (pin "4") (pinfunction "NC_4") (pintype "passive+no_connect"))
    )
    (net (code "90") (name "unconnected-(M1-NC-Pad13)") (class "Default")
      (node (ref "M1") (pin "13") (pinfunction "NC_13") (pintype "passive+no_connect"))
    )
    (net (code "91") (name "unconnected-(M1-NC-PadB5)") (class "Default")
      (node (ref "M1") (pin "B5") (pinfunction "NC_B5") (pintype "passive+no_connect"))
    )
    (net (code "92") (name "unconnected-(M1-NC-PadC1)") (class "Default")
      (node (ref "M1") (pin "C1") (pinfunction "NC_C1") (pintype "passive+no_connect"))
    )
    (net (code "93") (name "unconnected-(M1-NC-PadC3)") (class "Default")
      (node (ref "M1") (pin "C3") (pinfunction "NC_C3") (pintype "passive+no_connect"))
    )
    (net (code "94") (name "unconnected-(M1-NC-PadC4)") (class "Default")
      (node (ref "M1") (pin "C4") (pinfunction "NC_C4") (pintype "passive+no_connect"))
    )
    (net (code "95") (name "unconnected-(M1-NC-PadD3)") (class "Default")
      (node (ref "M1") (pin "D3") (pinfunction "NC_D3") (pintype "passive+no_connect"))
    )
    (net (code "96") (name "unconnected-(M1-NC-PadD4)") (class "Default")
      (node (ref "M1") (pin "D4") (pinfunction "NC_D4") (pintype "passive+no_connect"))
    )
    (net (code "97") (name "unconnected-(M1-NC-PadF5)") (class "Default")
      (node (ref "M1") (pin "F5") (pinfunction "NC_F5") (pintype "passive+no_connect"))
    )
    (net (code "98") (name "unconnected-(M1-P0.02{slash}NFC1-Pad7)") (class "Default")
      (node (ref "M1") (pin "7") (pinfunction "P0.02/NFC1_7") (pintype "bidirectional+no_connect"))
    )
    (net (code "99") (name "unconnected-(M1-P0.03{slash}NFC2-Pad8)") (class "Default")
      (node (ref "M1") (pin "8") (pinfunction "P0.03/NFC2_8") (pintype "bidirectional+no_connect"))
    )
    (net (code "100") (name "unconnected-(M1-P0.06{slash}AIN2-PadA1)") (class "Default")
      (node (ref "M1") (pin "A1") (pinfunction "P0.06/AIN2_A1") (pintype "bidirectional+no_connect"))
    )
    (net (code "101") (name "unconnected-(M1-P0.07{slash}AIN3-PadA2)") (class "Default")
      (node (ref "M1") (pin "A2") (pinfunction "P0.07/AIN3_A2") (pintype "bidirectional+no_connect"))
    )
    (net (code "102") (name "unconnected-(M1-P0.08{slash}SCK-PadA3)") (class "Default")
      (node (ref "M1") (pin "A3") (pinfunction "P0.08/SCK_A3") (pintype "bidirectional+no_connect"))
    )
    (net (code "103") (name "unconnected-(M1-P0.09{slash}MOSI-Pad11)") (class "Default")
      (node (ref "M1") (pin "11") (pinfunction "P0.09/MOSI_11") (pintype "bidirectional+no_connect"))
    )
    (net (code "104") (name "unconnected-(M1-P0.10{slash}MISO-PadE6)") (class "Default")
      (node (ref "M1") (pin "E6") (pinfunction "P0.10/MISO_E6") (pintype "bidirectional+no_connect"))
    )
    (net (code "105") (name "unconnected-(M1-P0.11-Pad12)") (class "Default")
      (node (ref "M1") (pin "12") (pinfunction "P0.11_12") (pintype "bidirectional+no_connect"))
    )
    (net (code "106") (name "unconnected-(M1-P0.13{slash}IO0-PadB6)") (class "Default")
      (node (ref "M1") (pin "B6") (pinfunction "P0.13/IO0_B6") (pintype "bidirectional+no_connect"))
    )
    (net (code "107") (name "unconnected-(M1-P0.14{slash}IO1-PadB3)") (class "Default")
      (node (ref "M1") (pin "B3") (pinfunction "P0.14/IO1_B3") (pintype "bidirectional+no_connect"))
    )
    (net (code "108") (name "unconnected-(M1-P0.15{slash}IO2-PadB4)") (class "Default")
      (node (ref "M1") (pin "B4") (pinfunction "P0.15/IO2_B4") (pintype "bidirectional+no_connect"))
    )
    (net (code "109") (name "unconnected-(M1-P0.16{slash}IO3-PadA4)") (class "Default")
      (node (ref "M1") (pin "A4") (pinfunction "P0.16/IO3_A4") (pintype "bidirectional+no_connect"))
    )
    (net (code "110") (name "unconnected-(M1-P0.17{slash}SCK-PadB2)") (class "Default")
      (node (ref "M1") (pin "B2") (pinfunction "P0.17/SCK_B2") (pintype "bidirectional+no_connect"))
    )
    (net (code "111") (name "unconnected-(M1-P0.18{slash}CSN-PadF3)") (class "Default")
      (node (ref "M1") (pin "F3") (pinfunction "P0.18/CSN_F3") (pintype "bidirectional+no_connect"))
    )
    (net (code "112") (name "unconnected-(M1-P0.19-PadB1)") (class "Default")
      (node (ref "M1") (pin "B1") (pinfunction "P0.19_B1") (pintype "bidirectional+no_connect"))
    )
    (net (code "113") (name "unconnected-(M1-P0.20-PadC5)") (class "Default")
      (node (ref "M1") (pin "C5") (pinfunction "P0.20_C5") (pintype "bidirectional+no_connect"))
    )
    (net (code "114") (name "unconnected-(M1-P0.21-PadC2)") (class "Default")
      (node (ref "M1") (pin "C2") (pinfunction "P0.21_C2") (pintype "bidirectional+no_connect"))
    )
    (net (code "115") (name "unconnected-(M1-P0.22-PadD5)") (class "Default")
      (node (ref "M1") (pin "D5") (pinfunction "P0.22_D5") (pintype "bidirectional+no_connect"))
    )
    (net (code "116") (name "unconnected-(M1-P0.25{slash}AIN4-PadC6)") (class "Default")
      (node (ref "M1") (pin "C6") (pinfunction "P0.25/AIN4_C6") (pintype "bidirectional+no_connect"))
    )
    (net (code "117") (name "unconnected-(M1-P0.26{slash}AIN5-PadD1)") (class "Default")
      (node (ref "M1") (pin "D1") (pinfunction "P0.26/AIN5_D1") (pintype "bidirectional+no_connect"))
    )
    (net (code "118") (name "unconnected-(M1-P0.27{slash}AIN6-PadD2)") (class "Default")
      (node (ref "M1") (pin "D2") (pinfunction "P0.27/AIN6_D2") (pintype "bidirectional+no_connect"))
    )
    (net (code "119") (name "unconnected-(M1-P1.00-PadA5)") (class "Default")
      (node (ref "M1") (pin "A5") (pinfunction "P1.00_A5") (pintype "bidirectional+no_connect"))
    )
    (net (code "120") (name "unconnected-(M1-P1.01-PadD6)") (class "Default")
      (node (ref "M1") (pin "D6") (pinfunction "P1.01_D6") (pintype "bidirectional+no_connect"))
    )
    (net (code "121") (name "unconnected-(M1-P1.02-Pad1)") (class "Default")
      (node (ref "M1") (pin "1") (pinfunction "P1.02_1") (pintype "bidirectional+no_connect"))
    )
    (net (code "122") (name "unconnected-(M1-P1.03-Pad2)") (class "Default")
      (node (ref "M1") (pin "2") (pinfunction "P1.03_2") (pintype "bidirectional+no_connect"))
    )
    (net (code "123") (name "unconnected-(M1-P1.05-PadE1)") (class "Default")
      (node (ref "M1") (pin "E1") (pinfunction "P1.05_E1") (pintype "bidirectional+no_connect"))
    )
    (net (code "124") (name "unconnected-(M1-P1.07-PadE3)") (class "Default")
      (node (ref "M1") (pin "E3") (pinfunction "P1.07_E3") (pintype "bidirectional+no_connect"))
    )
    (net (code "125") (name "unconnected-(M1-P1.08-PadA6)") (class "Default")
      (node (ref "M1") (pin "A6") (pinfunction "P1.08_A6") (pintype "bidirectional+no_connect"))
    )
    (net (code "126") (name "unconnected-(M1-P1.10-PadZ1)") (class "Default")
      (node (ref "M1") (pin "Z1") (pinfunction "P1.10_Z1") (pintype "bidirectional+no_connect"))
    )
    (net (code "127") (name "unconnected-(M1-P1.11-PadZ2)") (class "Default")
      (node (ref "M1") (pin "Z2") (pinfunction "P1.11_Z2") (pintype "bidirectional+no_connect"))
    )
    (net (code "128") (name "unconnected-(M1-P1.12-PadZ3)") (class "Default")
      (node (ref "M1") (pin "Z3") (pinfunction "P1.12_Z3") (pintype "bidirectional+no_connect"))
    )
    (net (code "129") (name "unconnected-(M1-P1.13-PadZ4)") (class "Default")
      (node (ref "M1") (pin "Z4") (pinfunction "P1.13_Z4") (pintype "bidirectional+no_connect"))
    )
    (net (code "130") (name "unconnected-(M1-P1.14-PadZ5)") (class "Default")
      (node (ref "M1") (pin "Z5") (pinfunction "P1.14_Z5") (pintype "bidirectional+no_connect"))
    )
    (net (code "131") (name "unconnected-(M1-P1.15-PadZ6)") (class "Default")
      (node (ref "M1") (pin "Z6") (pinfunction "P1.15_Z6") (pintype "bidirectional+no_connect"))
    )
    (net (code "132") (name "unconnected-(M1-VBUS-PadF6)") (class "Default")
      (node (ref "M1") (pin "F6") (pinfunction "VBUS_F6") (pintype "power_in+no_connect"))
    )
    (net (code "133") (name "unconnected-(M2-GPIO1{slash}XTAL_32K_N{slash}LP_GPIO1{slash}LP_UART_DSRN{slash}ADC1_CH1-Pad13)") (class "Default")
      (node (ref "M2") (pin "13") (pinfunction "GPIO1/XTAL_32K_N/LP_GPIO1/LP_UART_DSRN/ADC1_CH1_13") (pintype "bidirectional+no_connect"))
    )
    (net (code "134") (name "unconnected-(M2-GPIO12{slash}USB_D--Pad17)") (class "Default")
      (node (ref "M2") (pin "17") (pinfunction "GPIO12/USB_D-_17") (pintype "bidirectional+no_connect"))
    )
    (net (code "135") (name "unconnected-(M2-GPIO13{slash}USB_D+-Pad18)") (class "Default")
      (node (ref "M2") (pin "18") (pinfunction "GPIO13/USB_D+_18") (pintype "bidirectional+no_connect"))
    )
    (net (code "136") (name "unconnected-(M2-GPIO14-Pad19)") (class "Default")
      (node (ref "M2") (pin "19") (pinfunction "GPIO14_19") (pintype "bidirectional+no_connect"))
    )
    (net (code "137") (name "unconnected-(M2-GPIO15-Pad20)") (class "Default")
      (node (ref "M2") (pin "20") (pinfunction "GPIO15_20") (pintype "bidirectional+no_connect"))
    )
    (net (code "138") (name "unconnected-(M2-GPIO18{slash}SDIO_CMD{slash}FSPICS2-Pad24)") (class "Default")
      (node (ref "M2") (pin "24") (pinfunction "GPIO18/SDIO_CMD/FSPICS2_24") (pintype "bidirectional+no_connect"))
    )
    (net (code "139") (name "unconnected-(M2-GPIO19{slash}SDIO_CLK{slash}FSPICS3-Pad25)") (class "Default")
      (node (ref "M2") (pin "25") (pinfunction "GPIO19/SDIO_CLK/FSPICS3_25") (pintype "bidirectional+no_connect"))
    )
    (net (code "140") (name "unconnected-(M2-GPIO20{slash}SDIO_DATA0{slash}FSPICS4-Pad26)") (class "Default")
      (node (ref "M2") (pin "26") (pinfunction "GPIO20/SDIO_DATA0/FSPICS4_26") (pintype "bidirectional+no_connect"))
    )
    (net (code "141") (name "unconnected-(M2-GPIO21{slash}SDIO_DATA1{slash}FSPICS5-Pad27)") (class "Default")
      (node (ref "M2") (pin "27") (pinfunction "GPIO21/SDIO_DATA1/FSPICS5_27") (pintype "bidirectional+no_connect"))
    )
    (net (code "142") (name "unconnected-(M2-GPIO22{slash}SDIO_DATA2-Pad28)") (class "Default")
      (node (ref "M2") (pin "28") (pinfunction "GPIO22/SDIO_DATA2_28") (pintype "bidirectional+no_connect"))
    )
    (net (code "143") (name "unconnected-(M2-GPIO23{slash}SDIO_DATA3-Pad29)") (class "Default")
      (node (ref "M2") (pin "29") (pinfunction "GPIO23/SDIO_DATA3_29") (pintype "bidirectional+no_connect"))
    )
    (net (code "144") (name "unconnected-(M2-MTCK{slash}GPIO6{slash}LP_GPIO6{slash}LP_I2C_SDA{slash}ADC1_CH6{slash}FSPICLK-Pad15)") (class "Default")
      (node (ref "M2") (pin "15") (pinfunction "MTCK/GPIO6/LP_GPIO6/LP_I2C_SDA/ADC1_CH6/FSPICLK_15") (pintype "bidirectional+no_connect"))
    )
    (net (code "145") (name "unconnected-(M2-MTDI{slash}GPIO5{slash}LP_GPIO5{slash}LP_UART_TXD{slash}ADC1_CH5{slash}FSPIWP-Pad10)") (class "Default")
      (node (ref "M2") (pin "10") (pinfunction "MTDI/GPIO5/LP_GPIO5/LP_UART_TXD/ADC1_CH5/FSPIWP_10") (pintype "bidirectional+no_connect"))
    )
    (net (code "146") (name "unconnected-(M2-MTDO{slash}GPIO7{slash}LP_GPIO7{slash}LP_I2C_SCL{slash}FSPID-Pad16)") (class "Default")
      (node (ref "M2") (pin "16") (pinfunction "MTDO/GPIO7/LP_GPIO7/LP_I2C_SCL/FSPID_16") (pintype "bidirectional+no_connect"))
    )
    (net (code "147") (name "unconnected-(M2-MTMS{slash}GPIO4{slash}LP_GPIO4{slash}LP_UART_RXD{slash}ADC1_CH4{slash}FSPIHD-Pad9)") (class "Default")
      (node (ref "M2") (pin "9") (pinfunction "MTMS/GPIO4/LP_GPIO4/LP_UART_RXD/ADC1_CH4/FSPIHD_9") (pintype "bidirectional+no_connect"))
    )
    (net (code "148") (name "unconnected-(M2-NC-Pad4)") (class "Default")
      (node (ref "M2") (pin "4") (pinfunction "NC_4") (pintype "passive+no_connect"))
    )
    (net (code "149") (name "unconnected-(M2-NC-Pad7)") (class "Default")
      (node (ref "M2") (pin "7") (pinfunction "NC_7") (pintype "passive+no_connect"))
    )
    (net (code "150") (name "unconnected-(M2-NC-Pad21)") (class "Default")
      (node (ref "M2") (pin "21") (pinfunction "NC_21") (pintype "passive+no_connect"))
    )
    (net (code "151") (name "unconnected-(M2-NC-Pad32)") (class "Default")
      (node (ref "M2") (pin "32") (pinfunction "NC_32") (pintype "passive+no_connect"))
    )
    (net (code "152") (name "unconnected-(M2-NC-Pad33)") (class "Default")
      (node (ref "M2") (pin "33") (pinfunction "NC_33") (pintype "passive+no_connect"))
    )
    (net (code "153") (name "unconnected-(M2-NC-Pad34)") (class "Default")
      (node (ref "M2") (pin "34") (pinfunction "NC_34") (pintype "passive+no_connect"))
    )
    (net (code "154") (name "unconnected-(M2-NC-Pad35)") (class "Default")
      (node (ref "M2") (pin "35") (pinfunction "NC_35") (pintype "passive+no_connect"))
    )
    (net (code "155") (name "unconnected-(U7-ADC1-Pad16)") (class "Default")
      (node (ref "U7") (pin "16") (pinfunction "ADC1_16") (pintype "input+no_connect"))
    )
    (net (code "156") (name "unconnected-(U7-ADC2-Pad15)") (class "Default")
      (node (ref "U7") (pin "15") (pinfunction "ADC2_15") (pintype "input+no_connect"))
    )
    (net (code "157") (name "unconnected-(U7-ADC3-Pad13)") (class "Default")
      (node (ref "U7") (pin "13") (pinfunction "ADC3_13") (pintype "input+no_connect"))
    )
    (net (code "158") (name "unconnected-(U7-INT1-Pad11)") (class "Default")
      (node (ref "U7") (pin "11") (pinfunction "INT1_11") (pintype "output+no_connect"))
    )
    (net (code "159") (name "unconnected-(U7-INT2-Pad9)") (class "Default")
      (node (ref "U7") (pin "9") (pinfunction "INT2_9") (pintype "output+no_connect"))
    )
    (net (code "160") (name "unconnected-(U7-NC-Pad2)") (class "Default")
      (node (ref "U7") (pin "2") (pinfunction "NC_2") (pintype "power_in+no_connect"))
    )
    (net (code "161") (name "unconnected-(U7-NC-Pad3)") (class "Default")
      (node (ref "U7") (pin "3") (pinfunction "NC_3") (pintype "power_in+no_connect"))
    )
    (net (code "162") (name "unconnected-(U8-INT-Pad5)") (class "Default")
      (node (ref "U8") (pin "5") (pinfunction "INT_5") (pintype "bidirectional+no_connect"))
    )
  )
)
